# airball_display_board_v1.net
KiCad netlist of a schematic drawn in EAGLE
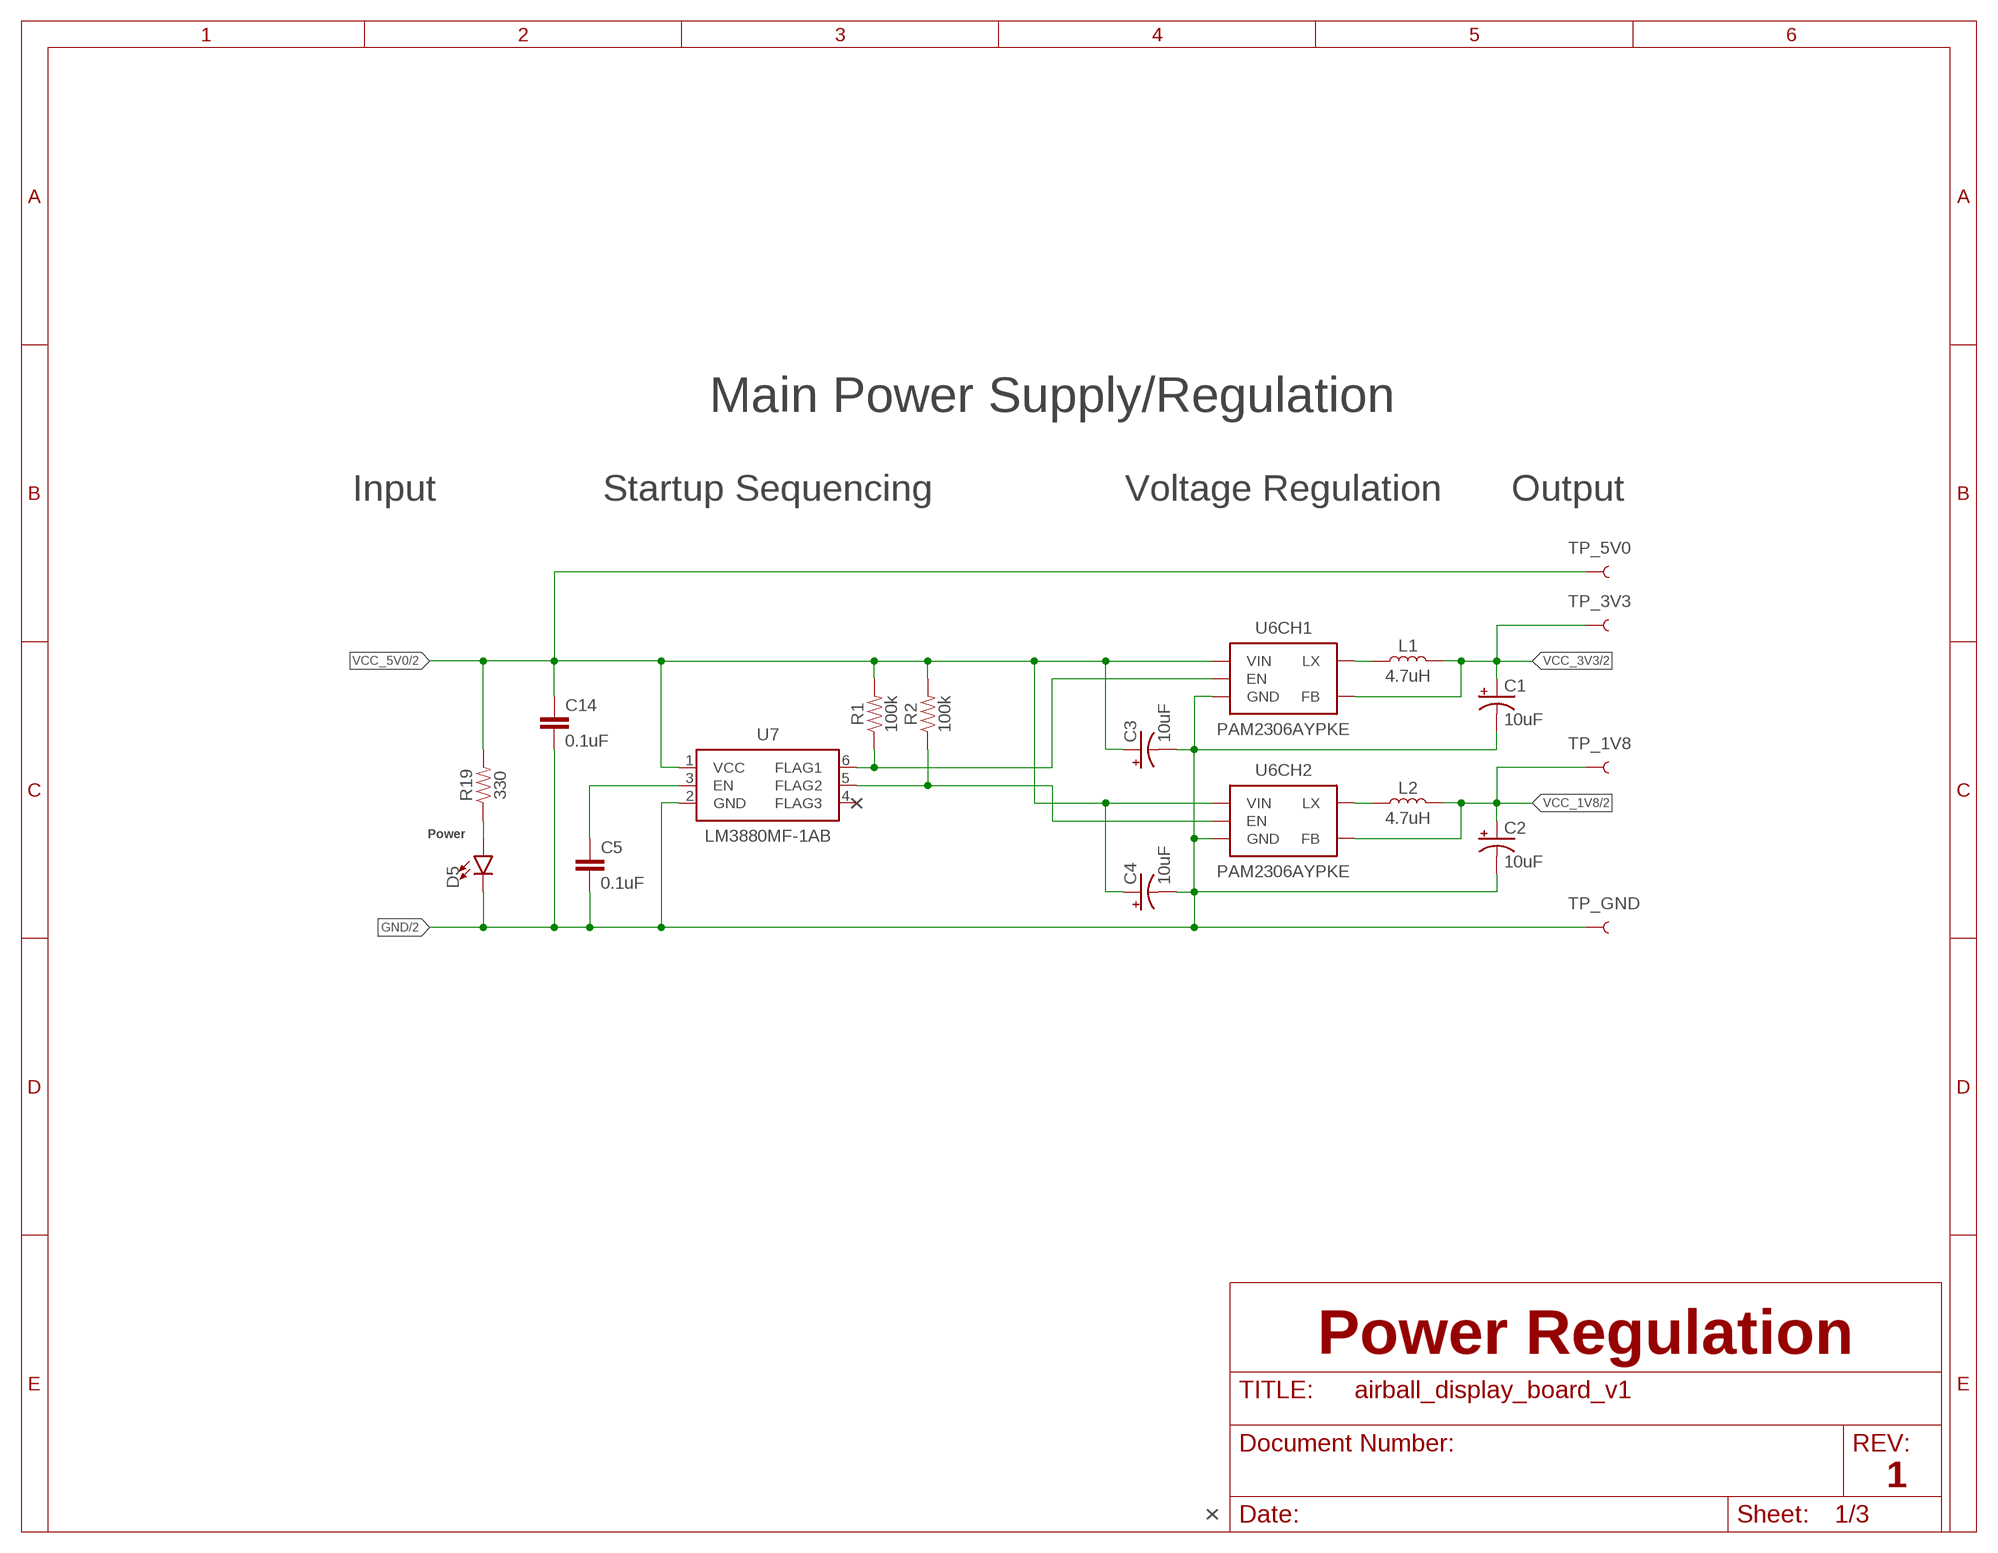
[diagram p0: schematic, sheet 1]
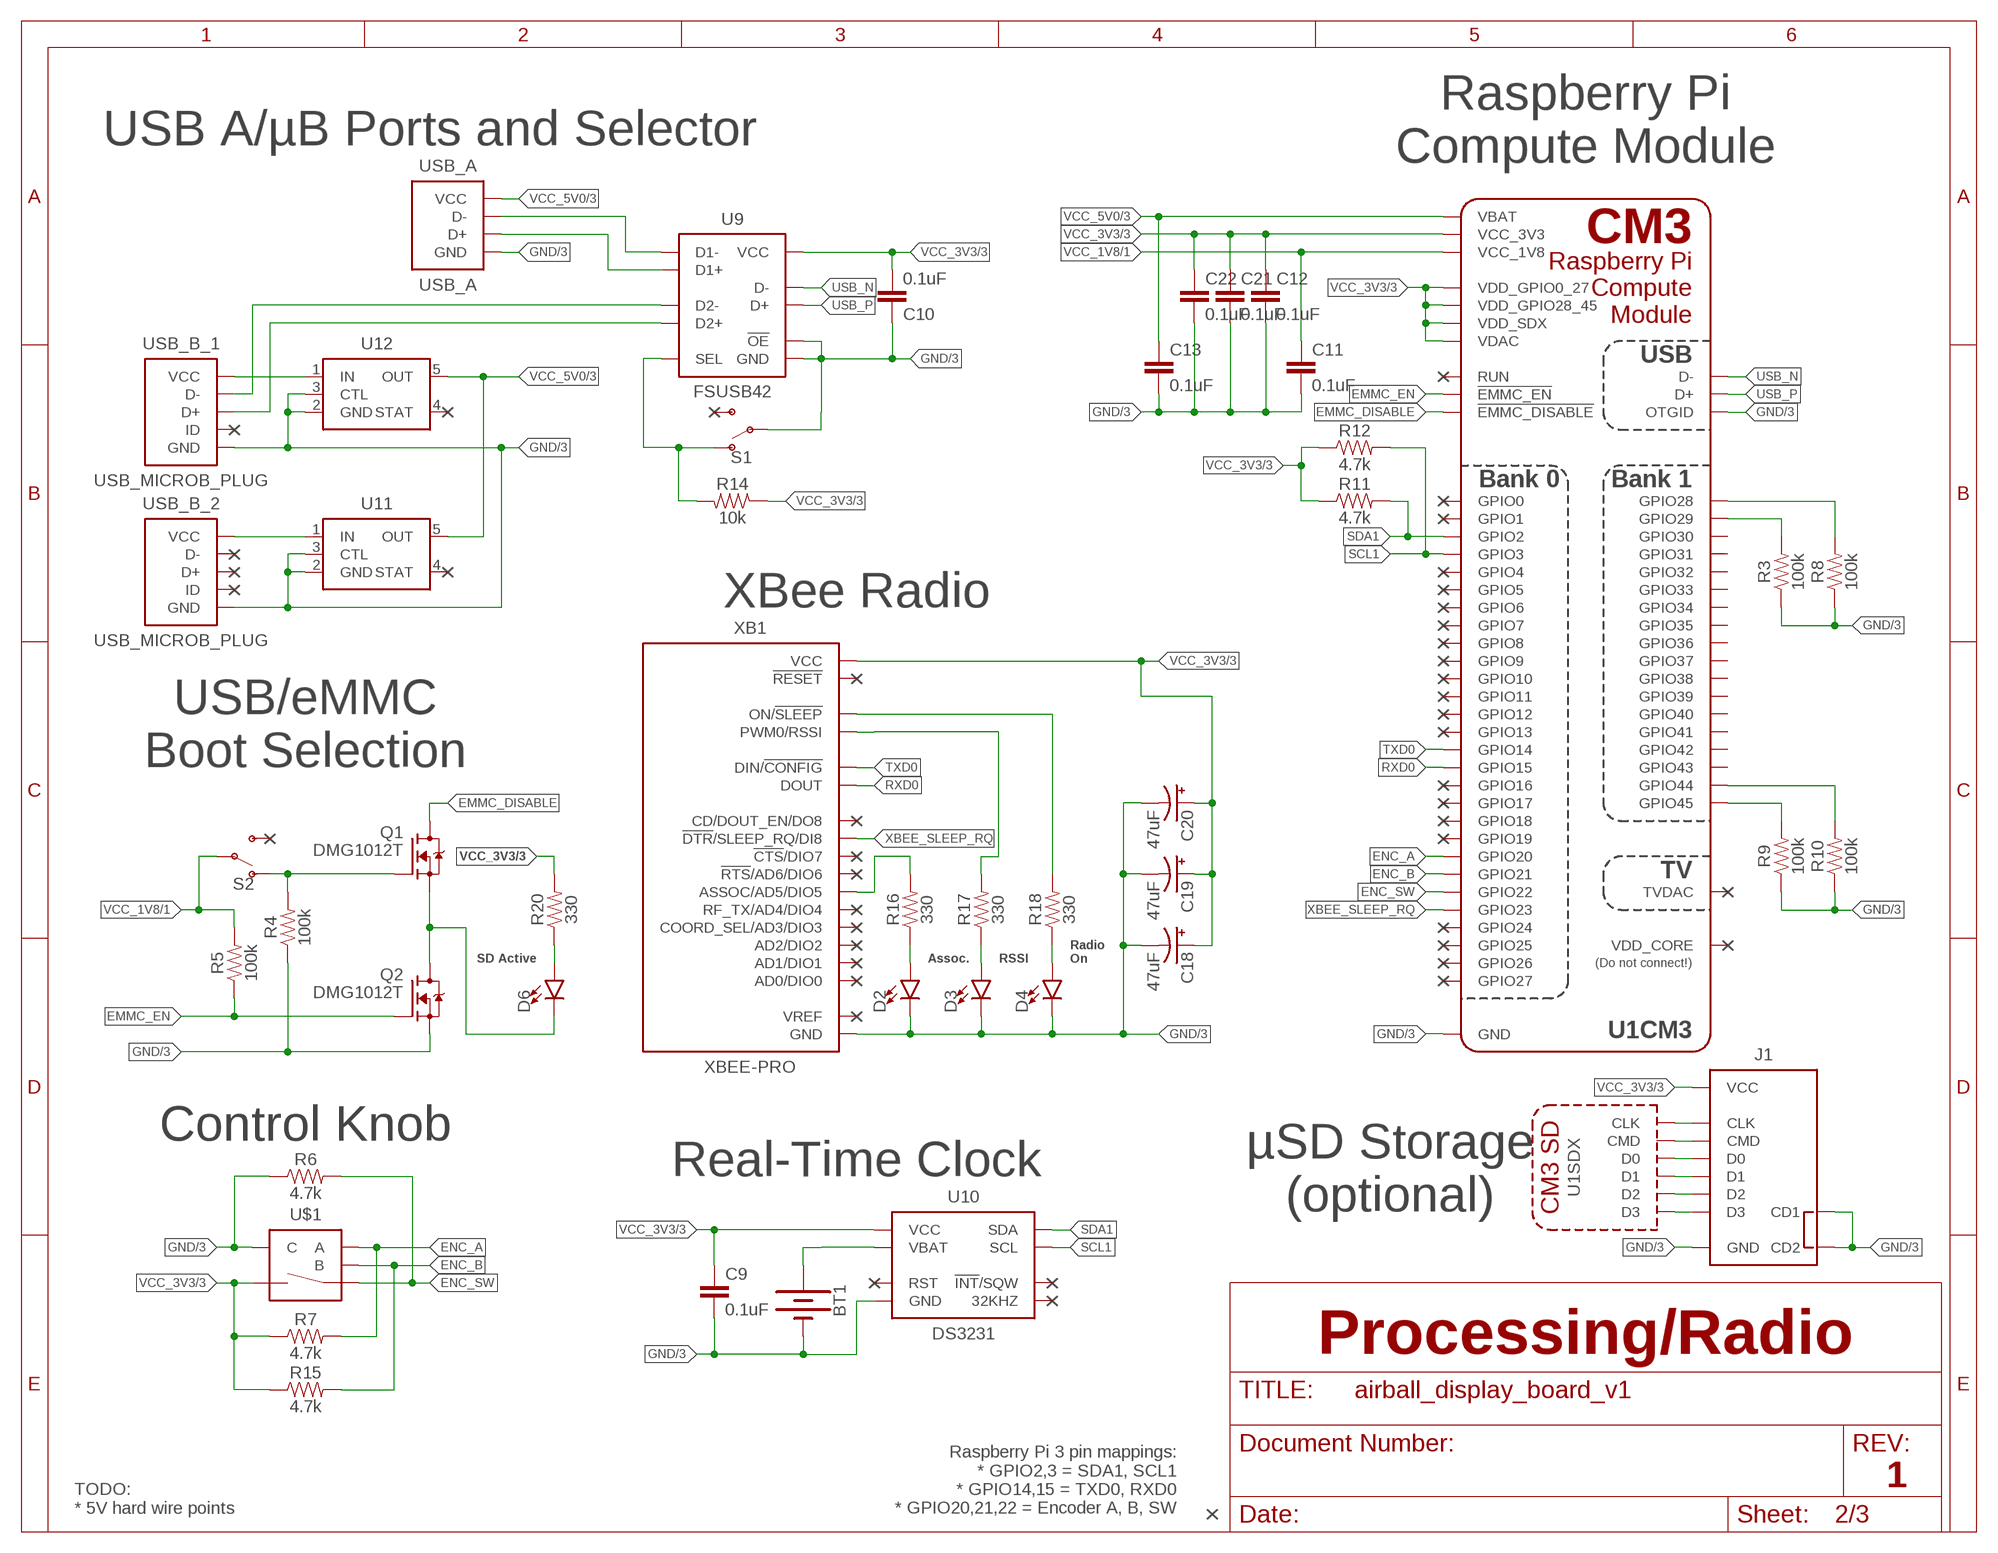
[diagram p1: schematic, sheet 2]
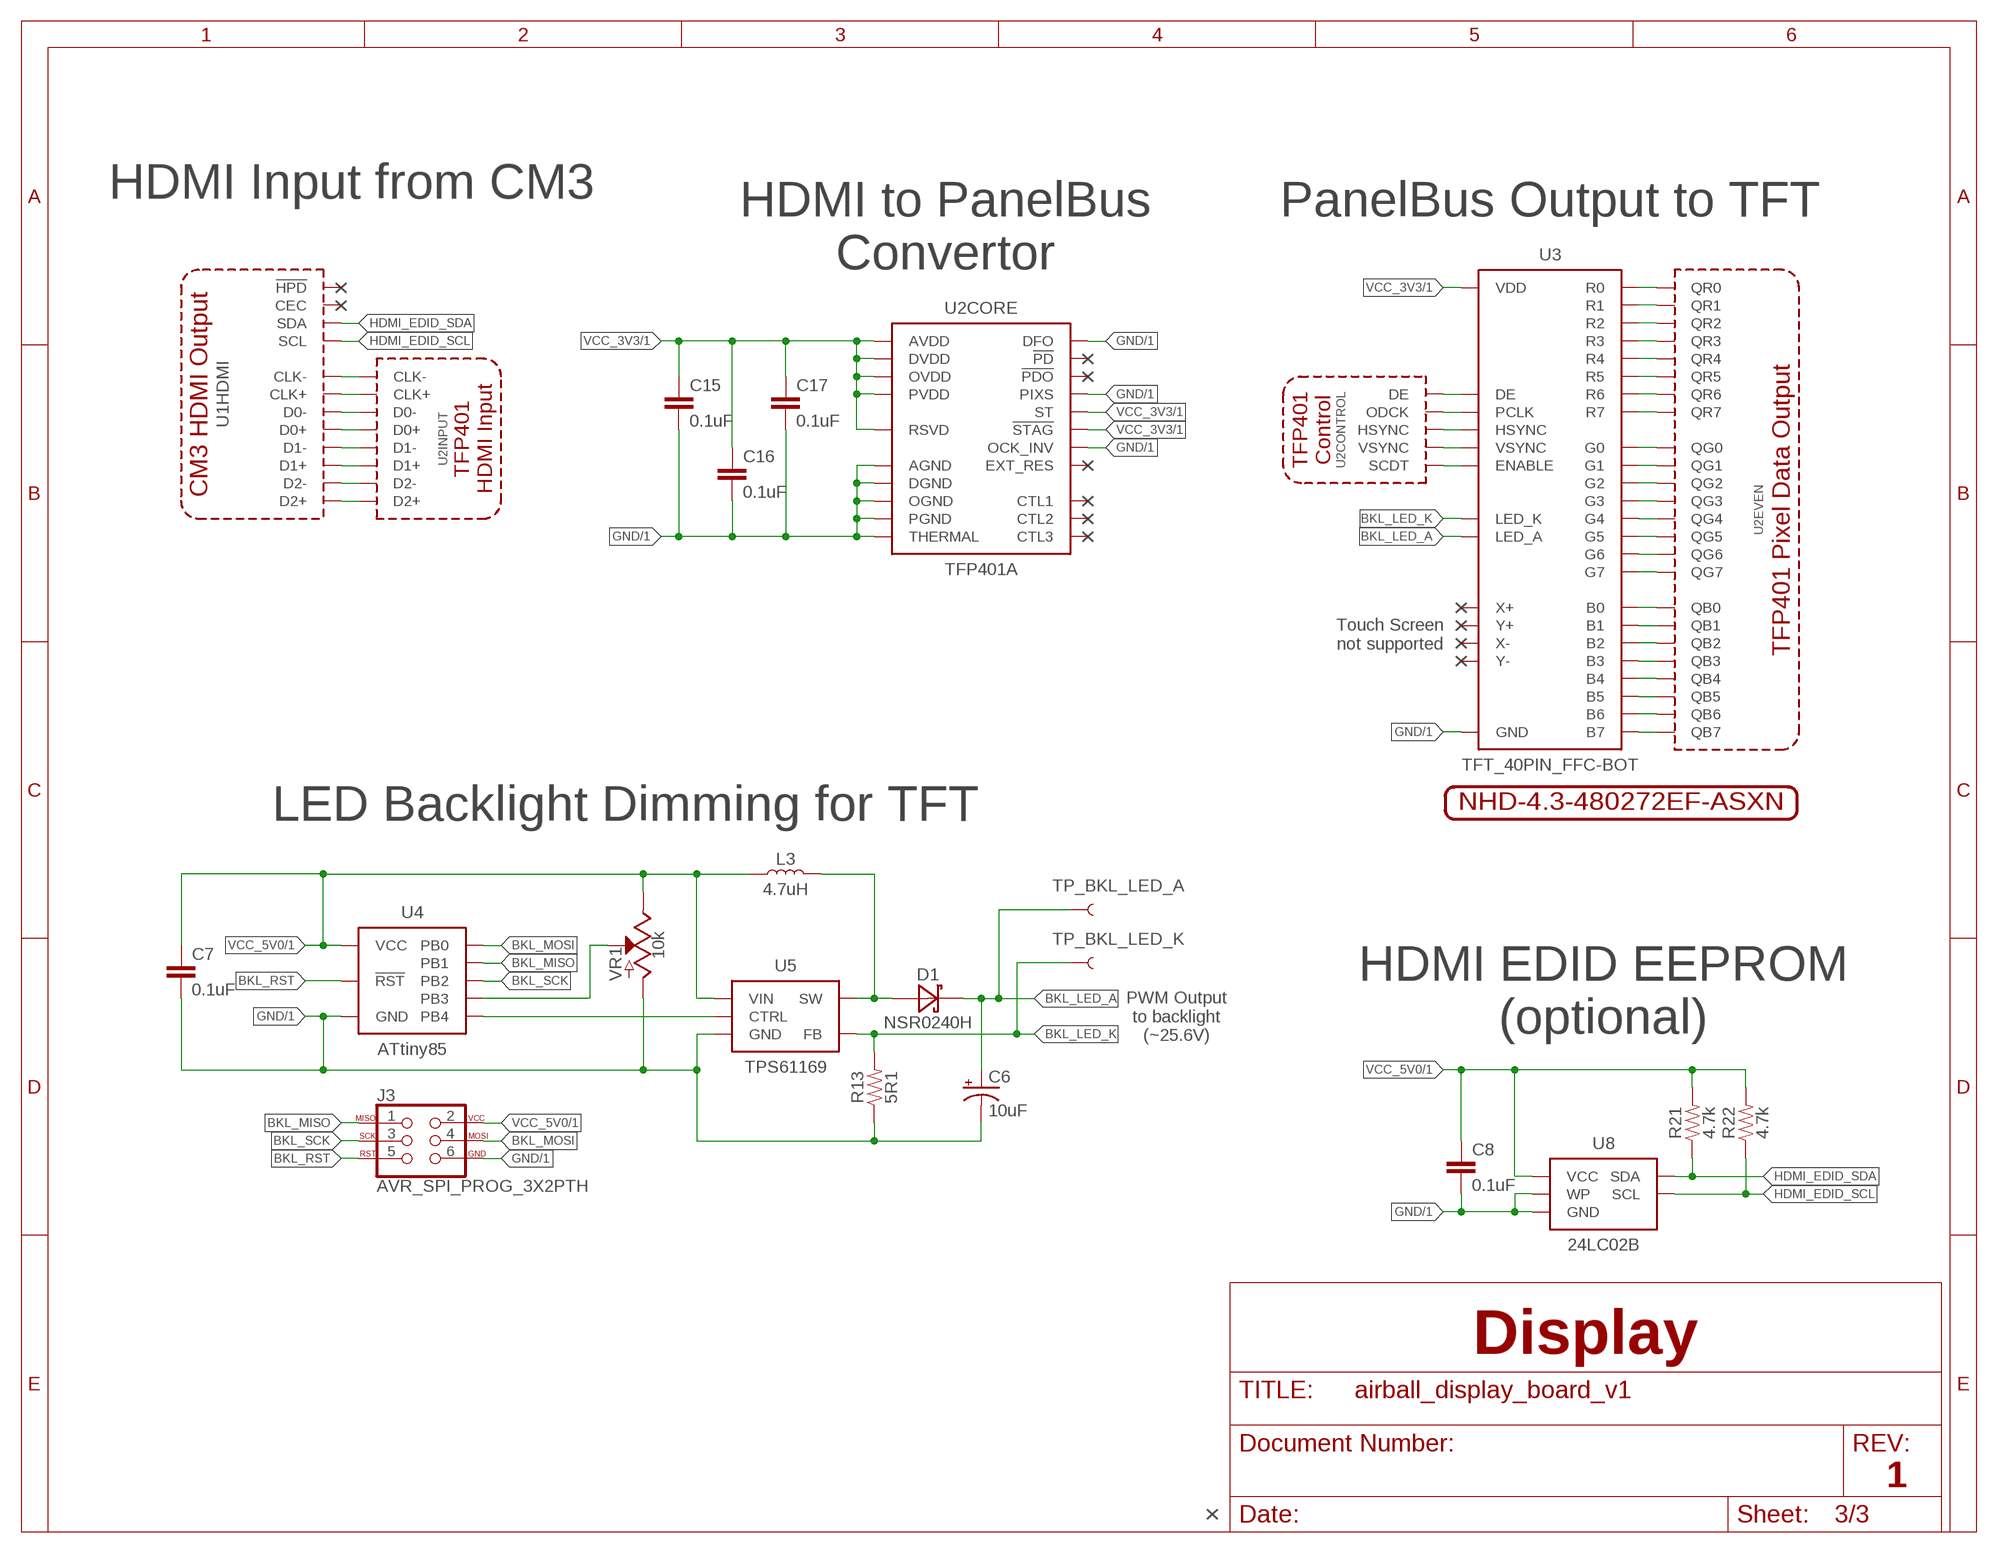
[diagram p2: schematic, sheet 3]

(export (version "E")
  (design (tool "Eeschema 10.0.6"))
  (components
    (comp (ref "BT1")
      (value "BATTERY-12MM_SMD")
      (footprint "eagle-import:BATTCON_12MM")
      (libsource (lib "eagle-import") (part "BATTERY-12MM_SMD"))
    )
    (comp (ref "C9")
      (value "0.1uF")
      (footprint "eagle-import:0603")
      (libsource (lib "eagle-import") (part "0.1UF-0603-25V-5%"))
    )
    (comp (ref "C10")
      (value "0.1uF")
      (footprint "eagle-import:0603")
      (libsource (lib "eagle-import") (part "0.1UF-0603-25V-5%"))
    )
    (comp (ref "C11")
      (value "0.1uF")
      (footprint "eagle-import:0603")
      (libsource (lib "eagle-import") (part "0.1UF-0603-25V-5%"))
    )
    (comp (ref "C12")
      (value "0.1uF")
      (footprint "eagle-import:0603")
      (libsource (lib "eagle-import") (part "0.1UF-0603-25V-5%"))
    )
    (comp (ref "C13")
      (value "0.1uF")
      (footprint "eagle-import:0603")
      (libsource (lib "eagle-import") (part "0.1UF-0603-25V-5%"))
    )
    (comp (ref "C18")
      (value "47uF")
      (footprint "eagle-import:EIA3528")
      (libsource (lib "eagle-import") (part "47UF-POLAR-EIA3528-10V-10%"))
    )
    (comp (ref "C19")
      (value "47uF")
      (footprint "eagle-import:EIA3528")
      (libsource (lib "eagle-import") (part "47UF-POLAR-EIA3528-10V-10%"))
    )
    (comp (ref "C20")
      (value "47uF")
      (footprint "eagle-import:EIA3528")
      (libsource (lib "eagle-import") (part "47UF-POLAR-EIA3528-10V-10%"))
    )
    (comp (ref "C21")
      (value "0.1uF")
      (footprint "eagle-import:0603")
      (libsource (lib "eagle-import") (part "0.1UF-0603-25V-5%"))
    )
    (comp (ref "C22")
      (value "0.1uF")
      (footprint "eagle-import:0603")
      (libsource (lib "eagle-import") (part "0.1UF-0603-25V-5%"))
    )
    (comp (ref "D2")
      (value "LED0603")
      (footprint "eagle-import:LED-0603")
      (libsource (lib "eagle-import") (part "LED0603"))
    )
    (comp (ref "D3")
      (value "LED0603")
      (footprint "eagle-import:LED-0603")
      (libsource (lib "eagle-import") (part "LED0603"))
    )
    (comp (ref "D4")
      (value "LED0603")
      (footprint "eagle-import:LED-0603")
      (libsource (lib "eagle-import") (part "LED0603"))
    )
    (comp (ref "D6")
      (value "LED0603")
      (footprint "eagle-import:LED-0603")
      (libsource (lib "eagle-import") (part "LED0603"))
    )
    (comp (ref "J1")
      (value "MICRO-SD-SD4-MOLEX_104031")
      (footprint "eagle-import:MOLEX_MICRO_SD_104031")
      (libsource (lib "eagle-import") (part "MICRO-SD-SD4-MOLEX_104031"))
    )
    (comp (ref "Q1")
      (value "DMG1012T")
      (footprint "eagle-import:SOT523-3")
      (libsource (lib "eagle-import") (part "DMG1012T"))
    )
    (comp (ref "Q2")
      (value "DMG1012T")
      (footprint "eagle-import:SOT523-3")
      (libsource (lib "eagle-import") (part "DMG1012T"))
    )
    (comp (ref "R3")
      (value "100k")
      (footprint "eagle-import:0603")
      (libsource (lib "eagle-import") (part "100KOHM-0603-1/10W-1%"))
    )
    (comp (ref "R4")
      (value "100k")
      (footprint "eagle-import:0603")
      (libsource (lib "eagle-import") (part "100KOHM-0603-1/10W-1%"))
    )
    (comp (ref "R5")
      (value "100k")
      (footprint "eagle-import:0603")
      (libsource (lib "eagle-import") (part "100KOHM-0603-1/10W-1%"))
    )
    (comp (ref "R6")
      (value "4.7k")
      (footprint "eagle-import:0603")
      (libsource (lib "eagle-import") (part "4.7KOHM-0603-1/10W-1%"))
    )
    (comp (ref "R7")
      (value "4.7k")
      (footprint "eagle-import:0603")
      (libsource (lib "eagle-import") (part "4.7KOHM-0603-1/10W-1%"))
    )
    (comp (ref "R8")
      (value "100k")
      (footprint "eagle-import:0603")
      (libsource (lib "eagle-import") (part "100KOHM-0603-1/10W-1%"))
    )
    (comp (ref "R9")
      (value "100k")
      (footprint "eagle-import:0603")
      (libsource (lib "eagle-import") (part "100KOHM-0603-1/10W-1%"))
    )
    (comp (ref "R10")
      (value "100k")
      (footprint "eagle-import:0603")
      (libsource (lib "eagle-import") (part "100KOHM-0603-1/10W-1%"))
    )
    (comp (ref "R11")
      (value "4.7k")
      (footprint "eagle-import:0603")
      (libsource (lib "eagle-import") (part "4.7KOHM-0603-1/10W-1%"))
    )
    (comp (ref "R12")
      (value "4.7k")
      (footprint "eagle-import:0603")
      (libsource (lib "eagle-import") (part "4.7KOHM-0603-1/10W-1%"))
    )
    (comp (ref "R14")
      (value "10k")
      (footprint "eagle-import:0603")
      (libsource (lib "eagle-import") (part "10KOHM-0603-1/10W-1%"))
    )
    (comp (ref "R15")
      (value "4.7k")
      (footprint "eagle-import:0603")
      (libsource (lib "eagle-import") (part "4.7KOHM-0603-1/10W-1%"))
    )
    (comp (ref "R16")
      (value "330")
      (footprint "eagle-import:0603")
      (libsource (lib "eagle-import") (part "330OHM-0603-1/10W-1%"))
    )
    (comp (ref "R17")
      (value "330")
      (footprint "eagle-import:0603")
      (libsource (lib "eagle-import") (part "330OHM-0603-1/10W-1%"))
    )
    (comp (ref "R18")
      (value "330")
      (footprint "eagle-import:0603")
      (libsource (lib "eagle-import") (part "330OHM-0603-1/10W-1%"))
    )
    (comp (ref "R20")
      (value "330")
      (footprint "eagle-import:0603")
      (libsource (lib "eagle-import") (part "330OHM-0603-1/10W-1%"))
    )
    (comp (ref "S1")
      (value "SWITCH-SPDT-SMD-RIGHT-ANGLE")
      (footprint "eagle-import:SWITCH_SPST_SMD_A")
      (libsource (lib "eagle-import") (part "SWITCH-SPDT-SMD-RIGHT-ANGLE"))
    )
    (comp (ref "S2")
      (value "SWITCH-SPDT-SMD-RIGHT-ANGLE")
      (footprint "eagle-import:SWITCH_SPST_SMD_A")
      (libsource (lib "eagle-import") (part "SWITCH-SPDT-SMD-RIGHT-ANGLE"))
    )
    (comp (ref "U$1")
      (value "ENCODER_WITH_SWITCH")
      (footprint "eagle-import:BOURNS_PEC11L")
      (libsource (lib "eagle-import") (part "ENCODER_WITH_SWITCH"))
    )
    (comp (ref "U1")
      (value "RPI_CM3-AMP_1473149")
      (footprint "eagle-import:AMP_1473149")
      (libsource (lib "eagle-import") (part "RPI_CM3-AMP_1473149"))
    )
    (comp (ref "U9")
      (value "FSUSB42")
      (footprint "eagle-import:MSOP10")
      (libsource (lib "eagle-import") (part "FSUSB42"))
    )
    (comp (ref "U10")
      (value "DS3231")
      (footprint "eagle-import:SOIC16W")
      (libsource (lib "eagle-import") (part "DS3231"))
    )
    (comp (ref "U11")
      (value "LTC4411")
      (footprint "eagle-import:SOT23-5")
      (libsource (lib "eagle-import") (part "LTC4411"))
    )
    (comp (ref "U12")
      (value "LTC4411")
      (footprint "eagle-import:SOT23-5")
      (libsource (lib "eagle-import") (part "LTC4411"))
    )
    (comp (ref "USB_A")
      (value "USB_A")
      (footprint "eagle-import:FCI_USB_A_87583")
      (libsource (lib "eagle-import") (part "USB_A"))
    )
    (comp (ref "USB_B_1")
      (value "USB_MICROB_PLUG")
      (footprint "eagle-import:USB_MICRO_B_TYCO")
      (libsource (lib "eagle-import") (part "USB_MICROB_PLUG"))
    )
    (comp (ref "USB_B_2")
      (value "USB_MICROB_PLUG")
      (footprint "eagle-import:USB_MICRO_B_TYCO")
      (libsource (lib "eagle-import") (part "USB_MICROB_PLUG"))
    )
    (comp (ref "XB1")
      (value "XBEE-PRO")
      (footprint "eagle-import:XBEE-PRO")
      (fields (field (name "MPN") "XBP24-AWI-001"))
      (libsource (lib "eagle-import") (part "XBEE-PRO"))
    )
    (comp (ref "C1")
      (value "10uF")
      (footprint "eagle-import:EIA3216")
      (libsource (lib "eagle-import") (part "10UF-POLAR-EIA3216-16V-10%(TANT)"))
    )
    (comp (ref "C2")
      (value "10uF")
      (footprint "eagle-import:EIA3216")
      (libsource (lib "eagle-import") (part "10UF-POLAR-EIA3216-16V-10%(TANT)"))
    )
    (comp (ref "C3")
      (value "10uF")
      (footprint "eagle-import:EIA3216")
      (libsource (lib "eagle-import") (part "10UF-POLAR-EIA3216-16V-10%(TANT)"))
    )
    (comp (ref "C4")
      (value "10uF")
      (footprint "eagle-import:EIA3216")
      (libsource (lib "eagle-import") (part "10UF-POLAR-EIA3216-16V-10%(TANT)"))
    )
    (comp (ref "C5")
      (value "0.1uF")
      (footprint "eagle-import:0603")
      (libsource (lib "eagle-import") (part "0.1UF-0603-25V-5%"))
    )
    (comp (ref "C14")
      (value "0.1uF")
      (footprint "eagle-import:0603")
      (libsource (lib "eagle-import") (part "0.1UF-0603-25V-5%"))
    )
    (comp (ref "D5")
      (value "LED0603")
      (footprint "eagle-import:LED-0603")
      (libsource (lib "eagle-import") (part "LED0603"))
    )
    (comp (ref "L1")
      (value "4.7uH")
      (footprint "eagle-import:INDUCTOR_SMD_4X4MM")
      (libsource (lib "eagle-import") (part "INDUCTOR-SMD_4X4"))
    )
    (comp (ref "L2")
      (value "4.7uH")
      (footprint "eagle-import:INDUCTOR_SMD_4X4MM")
      (libsource (lib "eagle-import") (part "INDUCTOR-SMD_4X4"))
    )
    (comp (ref "R1")
      (value "100k")
      (footprint "eagle-import:0603")
      (libsource (lib "eagle-import") (part "100KOHM-0603-1/10W-1%"))
    )
    (comp (ref "R2")
      (value "100k")
      (footprint "eagle-import:0603")
      (libsource (lib "eagle-import") (part "100KOHM-0603-1/10W-1%"))
    )
    (comp (ref "R19")
      (value "330")
      (footprint "eagle-import:0603")
      (libsource (lib "eagle-import") (part "330OHM-0603-1/10W-1%"))
    )
    (comp (ref "TP_1V8")
      (value "TEST-POINT3X5")
      (footprint "eagle-import:PAD.03X.05")
      (libsource (lib "eagle-import") (part "TEST-POINT3X5"))
    )
    (comp (ref "TP_3V3")
      (value "TEST-POINT3X5")
      (footprint "eagle-import:PAD.03X.05")
      (libsource (lib "eagle-import") (part "TEST-POINT3X5"))
    )
    (comp (ref "TP_5V0")
      (value "TEST-POINT3X5")
      (footprint "eagle-import:PAD.03X.05")
      (libsource (lib "eagle-import") (part "TEST-POINT3X5"))
    )
    (comp (ref "TP_GND")
      (value "TEST-POINT3X5")
      (footprint "eagle-import:PAD.03X.05")
      (libsource (lib "eagle-import") (part "TEST-POINT3X5"))
    )
    (comp (ref "U6")
      (value "PAM2306AYPKE")
      (footprint "eagle-import:WDFN12")
      (libsource (lib "eagle-import") (part "PAM2306"))
    )
    (comp (ref "U7")
      (value "LM3880MF-1AB")
      (footprint "eagle-import:SOT23-6")
      (libsource (lib "eagle-import") (part "LM3880"))
    )
    (comp (ref "C6")
      (value "10uF")
      (footprint "eagle-import:EIA3216")
      (libsource (lib "eagle-import") (part "10UF-POLAR-EIA3216-16V-10%(TANT)"))
    )
    (comp (ref "C7")
      (value "0.1uF")
      (footprint "eagle-import:0603")
      (libsource (lib "eagle-import") (part "0.1UF-0603-25V-5%"))
    )
    (comp (ref "C8")
      (value "0.1uF")
      (footprint "eagle-import:0603")
      (libsource (lib "eagle-import") (part "0.1UF-0603-25V-5%"))
    )
    (comp (ref "C15")
      (value "0.1uF")
      (footprint "eagle-import:0603")
      (libsource (lib "eagle-import") (part "0.1UF-0603-25V-5%"))
    )
    (comp (ref "C16")
      (value "0.1uF")
      (footprint "eagle-import:0603")
      (libsource (lib "eagle-import") (part "0.1UF-0603-25V-5%"))
    )
    (comp (ref "C17")
      (value "0.1uF")
      (footprint "eagle-import:0603")
      (libsource (lib "eagle-import") (part "0.1UF-0603-25V-5%"))
    )
    (comp (ref "D1")
      (value "NSR0240H")
      (footprint "eagle-import:SOD323")
      (libsource (lib "eagle-import") (part "DIODE-SCHOTTKY-SOD323"))
    )
    (comp (ref "J3")
      (value "AVR_SPI_PROG_3X2PTH")
      (footprint "eagle-import:2X3")
      (libsource (lib "eagle-import") (part "AVR_SPI_PROG_3X2PTH"))
    )
    (comp (ref "L3")
      (value "4.7uH")
      (footprint "eagle-import:INDUCTOR_SMD_4X4MM")
      (libsource (lib "eagle-import") (part "INDUCTOR-SMD_4X4"))
    )
    (comp (ref "R13")
      (value "5R1")
      (footprint "eagle-import:0603")
      (libsource (lib "eagle-import") (part "RESISTOR0603"))
    )
    (comp (ref "R21")
      (value "4.7k")
      (footprint "eagle-import:0603")
      (libsource (lib "eagle-import") (part "4.7KOHM-0603-1/10W-1%"))
    )
    (comp (ref "R22")
      (value "4.7k")
      (footprint "eagle-import:0603")
      (libsource (lib "eagle-import") (part "4.7KOHM-0603-1/10W-1%"))
    )
    (comp (ref "TP_BKL_LED_A")
      (value "TEST-POINT3X5")
      (footprint "eagle-import:PAD.03X.05")
      (libsource (lib "eagle-import") (part "TEST-POINT3X5"))
    )
    (comp (ref "TP_BKL_LED_K")
      (value "TEST-POINT3X5")
      (footprint "eagle-import:PAD.03X.05")
      (libsource (lib "eagle-import") (part "TEST-POINT3X5"))
    )
    (comp (ref "U$4")
      (value "NHD-4.3-480272EF-ASXN")
      (footprint "eagle-import:NHD-4.3-480272EF-ASXN")
      (libsource (lib "eagle-import") (part "NHD-4.3-480272EF-ASXN"))
    )
    (comp (ref "U2")
      (value "TFP401A")
      (footprint "eagle-import:TQFP100_POWER_LITE")
      (libsource (lib "eagle-import") (part "TFP401-POWER_LITE"))
    )
    (comp (ref "U3")
      (value "TFT_40PIN_FFC-BOT")
      (footprint "eagle-import:HIROSE_FFC40_FH12-40S-0.5SH")
      (libsource (lib "eagle-import") (part "TFT_40PIN_FFC-BOT"))
    )
    (comp (ref "U4")
      (value "ATtiny85")
      (footprint "eagle-import:SOIC8-5.4")
      (libsource (lib "eagle-import") (part "ATTINY25/45/85"))
    )
    (comp (ref "U5")
      (value "TPS61169")
      (footprint "eagle-import:SOT353-5")
      (libsource (lib "eagle-import") (part "TPS61169"))
    )
    (comp (ref "U8")
      (value "24LC02B")
      (footprint "eagle-import:SOT23-5")
      (libsource (lib "eagle-import") (part "24LC02B"))
    )
    (comp (ref "VR1")
      (value "10k")
      (footprint "eagle-import:BOURNS_PTV09A")
      (libsource (lib "eagle-import") (part "POTENTIOMETERPTV09A"))
    )
  )
  (nets
    (net (code "1") (name "BKL_LED_A") (class "Default")
      (node (ref "C6") (pin "+") (pinfunction "+_+") (pintype "passive"))
      (node (ref "D1") (pin "K") (pinfunction "C_K") (pintype "passive"))
      (node (ref "TP_BKL_LED_A") (pin "P$1") (pinfunction "1_P$1") (pintype "bidirectional"))
      (node (ref "U3") (pin "2") (pinfunction "LED_A_2") (pintype "power_in"))
    )
    (net (code "2") (name "BKL_LED_K") (class "Default")
      (node (ref "R13") (pin "2") (pinfunction "2_2") (pintype "passive"))
      (node (ref "TP_BKL_LED_K") (pin "P$1") (pinfunction "1_P$1") (pintype "bidirectional"))
      (node (ref "U3") (pin "1") (pinfunction "LED_K_1") (pintype "power_in"))
      (node (ref "U5") (pin "3") (pinfunction "FB_3") (pintype "input"))
    )
    (net (code "3") (name "BKL_MISO") (class "Default")
      (node (ref "J3") (pin "1") (pinfunction "1_1") (pintype "passive"))
      (node (ref "U4") (pin "6") (pinfunction "PB1_6") (pintype "bidirectional"))
    )
    (net (code "4") (name "BKL_MOSI") (class "Default")
      (node (ref "J3") (pin "4") (pinfunction "4_4") (pintype "passive"))
      (node (ref "U4") (pin "5") (pinfunction "PB0_5") (pintype "bidirectional"))
    )
    (net (code "5") (name "BKL_RST") (class "Default")
      (node (ref "J3") (pin "5") (pinfunction "5_5") (pintype "passive"))
      (node (ref "U4") (pin "1") (pinfunction "~{RST}_1") (pintype "input"))
    )
    (net (code "6") (name "BKL_SCK") (class "Default")
      (node (ref "J3") (pin "3") (pinfunction "3_3") (pintype "passive"))
      (node (ref "U4") (pin "7") (pinfunction "PB2_7") (pintype "bidirectional"))
    )
    (net (code "7") (name "EMMC_DISABLE") (class "Default")
      (node (ref "Q1") (pin "2") (pinfunction "D_2") (pintype "passive"))
      (node (ref "U1") (pin "2") (pinfunction "~{EMMC_DISABLE}_2") (pintype "input"))
    )
    (net (code "8") (name "EMMC_EN") (class "Default")
      (node (ref "Q2") (pin "1") (pinfunction "G_1") (pintype "passive"))
      (node (ref "R5") (pin "1") (pinfunction "1_1") (pintype "passive"))
      (node (ref "U1") (pin "90") (pinfunction "~{EMMC_EN}_90") (pintype "output"))
    )
    (net (code "9") (name "ENC_A") (class "Default")
      (node (ref "R7") (pin "2") (pinfunction "2_2") (pintype "passive"))
      (node (ref "U$1") (pin "A") (pinfunction "A_A") (pintype "output"))
      (node (ref "U1") (pin "69") (pinfunction "GPIO20_69") (pintype "bidirectional"))
    )
    (net (code "10") (name "ENC_B") (class "Default")
      (node (ref "R15") (pin "2") (pinfunction "2_2") (pintype "passive"))
      (node (ref "U$1") (pin "B") (pinfunction "B_B") (pintype "output"))
      (node (ref "U1") (pin "71") (pinfunction "GPIO21_71") (pintype "bidirectional"))
    )
    (net (code "11") (name "ENC_SW") (class "Default")
      (node (ref "R6") (pin "2") (pinfunction "2_2") (pintype "passive"))
      (node (ref "U$1") (pin "1") (pinfunction "SW+_1") (pintype "bidirectional"))
      (node (ref "U1") (pin "75") (pinfunction "GPIO22_75") (pintype "bidirectional"))
    )
    (net (code "12") (name "GND") (class "Default")
      (node (ref "BT1") (pin "GND") (pinfunction "-_GND") (pintype "power_in"))
      (node (ref "C1") (pin "-") (pinfunction "-_-") (pintype "passive"))
      (node (ref "C10") (pin "1") (pinfunction "1_1") (pintype "passive"))
      (node (ref "C11") (pin "2") (pinfunction "2_2") (pintype "passive"))
      (node (ref "C12") (pin "2") (pinfunction "2_2") (pintype "passive"))
      (node (ref "C13") (pin "2") (pinfunction "2_2") (pintype "passive"))
      (node (ref "C14") (pin "2") (pinfunction "2_2") (pintype "passive"))
      (node (ref "C15") (pin "2") (pinfunction "2_2") (pintype "passive"))
      (node (ref "C16") (pin "2") (pinfunction "2_2") (pintype "passive"))
      (node (ref "C17") (pin "2") (pinfunction "2_2") (pintype "passive"))
      (node (ref "C18") (pin "C") (pinfunction "-_C") (pintype "passive"))
      (node (ref "C19") (pin "C") (pinfunction "-_C") (pintype "passive"))
      (node (ref "C2") (pin "-") (pinfunction "-_-") (pintype "passive"))
      (node (ref "C20") (pin "C") (pinfunction "-_C") (pintype "passive"))
      (node (ref "C21") (pin "2") (pinfunction "2_2") (pintype "passive"))
      (node (ref "C22") (pin "2") (pinfunction "2_2") (pintype "passive"))
      (node (ref "C3") (pin "-") (pinfunction "-_-") (pintype "passive"))
      (node (ref "C4") (pin "-") (pinfunction "-_-") (pintype "passive"))
      (node (ref "C5") (pin "2") (pinfunction "2_2") (pintype "passive"))
      (node (ref "C6") (pin "-") (pinfunction "-_-") (pintype "passive"))
      (node (ref "C7") (pin "2") (pinfunction "2_2") (pintype "passive"))
      (node (ref "C8") (pin "2") (pinfunction "2_2") (pintype "passive"))
      (node (ref "C9") (pin "2") (pinfunction "2_2") (pintype "passive"))
      (node (ref "D2") (pin "C") (pinfunction "C_C") (pintype "passive"))
      (node (ref "D3") (pin "C") (pinfunction "C_C") (pintype "passive"))
      (node (ref "D4") (pin "C") (pinfunction "C_C") (pintype "passive"))
      (node (ref "D5") (pin "C") (pinfunction "C_C") (pintype "passive"))
      (node (ref "J1") (pin "6") (pinfunction "GND_6") (pintype "power_in"))
      (node (ref "J1") (pin "CD1") (pinfunction "CD1_CD1") (pintype "bidirectional"))
      (node (ref "J1") (pin "CD2") (pinfunction "CD2_CD2") (pintype "bidirectional"))
      (node (ref "J1") (pin "SH@1") (pinfunction "GND_SH@1") (pintype "power_in"))
      (node (ref "J1") (pin "SH@2") (pinfunction "GND_SH@2") (pintype "power_in"))
      (node (ref "J1") (pin "SH@3") (pinfunction "GND_SH@3") (pintype "power_in"))
      (node (ref "J1") (pin "SH@4") (pinfunction "GND_SH@4") (pintype "power_in"))
      (node (ref "J3") (pin "6") (pinfunction "6_6") (pintype "passive"))
      (node (ref "Q2") (pin "3") (pinfunction "S_3") (pintype "passive"))
      (node (ref "R10") (pin "1") (pinfunction "1_1") (pintype "passive"))
      (node (ref "R13") (pin "1") (pinfunction "1_1") (pintype "passive"))
      (node (ref "R3") (pin "1") (pinfunction "1_1") (pintype "passive"))
      (node (ref "R4") (pin "1") (pinfunction "1_1") (pintype "passive"))
      (node (ref "R6") (pin "1") (pinfunction "1_1") (pintype "passive"))
      (node (ref "R8") (pin "1") (pinfunction "1_1") (pintype "passive"))
      (node (ref "R9") (pin "1") (pinfunction "1_1") (pintype "passive"))
      (node (ref "S1") (pin "2") (pinfunction "P_2") (pintype "passive"))
      (node (ref "TP_GND") (pin "P$1") (pinfunction "1_P$1") (pintype "bidirectional"))
      (node (ref "U$1") (pin "C") (pinfunction "C_C") (pintype "input"))
      (node (ref "U1") (pin "1") (pinfunction "GND_1") (pintype "power_in"))
      (node (ref "U1") (pin "103") (pinfunction "GND_103") (pintype "power_in"))
      (node (ref "U1") (pin "104") (pinfunction "GND_104") (pintype "power_in"))
      (node (ref "U1") (pin "109") (pinfunction "GND_109") (pintype "power_in"))
      (node (ref "U1") (pin "110") (pinfunction "GND_110") (pintype "power_in"))
      (node (ref "U1") (pin "115") (pinfunction "GND_115") (pintype "power_in"))
      (node (ref "U1") (pin "116") (pinfunction "GND_116") (pintype "power_in"))
      (node (ref "U1") (pin "121") (pinfunction "GND_121") (pintype "power_in"))
      (node (ref "U1") (pin "122") (pinfunction "GND_122") (pintype "power_in"))
      (node (ref "U1") (pin "127") (pinfunction "GND_127") (pintype "power_in"))
      (node (ref "U1") (pin "13") (pinfunction "GND_13") (pintype "power_in"))
      (node (ref "U1") (pin "133") (pinfunction "GND_133") (pintype "power_in"))
      (node (ref "U1") (pin "134") (pinfunction "GND_134") (pintype "power_in"))
      (node (ref "U1") (pin "139") (pinfunction "GND_139") (pintype "power_in"))
      (node (ref "U1") (pin "14") (pinfunction "GND_14") (pintype "power_in"))
      (node (ref "U1") (pin "140") (pinfunction "GND_140") (pintype "power_in"))
      (node (ref "U1") (pin "145") (pinfunction "GND_145") (pintype "power_in"))
      (node (ref "U1") (pin "146") (pinfunction "GND_146") (pintype "power_in"))
      (node (ref "U1") (pin "151") (pinfunction "GND_151") (pintype "power_in"))
      (node (ref "U1") (pin "152") (pinfunction "GND_152") (pintype "power_in"))
      (node (ref "U1") (pin "157") (pinfunction "GND_157") (pintype "power_in"))
      (node (ref "U1") (pin "163") (pinfunction "GND_163") (pintype "power_in"))
      (node (ref "U1") (pin "164") (pinfunction "GND_164") (pintype "power_in"))
      (node (ref "U1") (pin "168") (pinfunction "OTGID_168") (pintype "input"))
      (node (ref "U1") (pin "169") (pinfunction "GND_169") (pintype "power_in"))
      (node (ref "U1") (pin "170") (pinfunction "GND_170") (pintype "power_in"))
      (node (ref "U1") (pin "181") (pinfunction "GND_181") (pintype "power_in"))
      (node (ref "U1") (pin "182") (pinfunction "GND_182") (pintype "power_in"))
      (node (ref "U1") (pin "187") (pinfunction "GND_187") (pintype "power_in"))
      (node (ref "U1") (pin "188") (pinfunction "GND_188") (pintype "power_in"))
      (node (ref "U1") (pin "19") (pinfunction "GND_19") (pintype "power_in"))
      (node (ref "U1") (pin "195") (pinfunction "GND_195") (pintype "power_in"))
      (node (ref "U1") (pin "196") (pinfunction "GND_196") (pintype "power_in"))
      (node (ref "U1") (pin "20") (pinfunction "GND_20") (pintype "power_in"))
      (node (ref "U1") (pin "25") (pinfunction "GND_25") (pintype "power_in"))
      (node (ref "U1") (pin "26") (pinfunction "GND_26") (pintype "power_in"))
      (node (ref "U1") (pin "31") (pinfunction "GND_31") (pintype "power_in"))
      (node (ref "U1") (pin "32") (pinfunction "GND_32") (pintype "power_in"))
      (node (ref "U1") (pin "37") (pinfunction "GND_37") (pintype "power_in"))
      (node (ref "U1") (pin "38") (pinfunction "GND_38") (pintype "power_in"))
      (node (ref "U1") (pin "43") (pinfunction "GND_43") (pintype "power_in"))
      (node (ref "U1") (pin "44") (pinfunction "GND_44") (pintype "power_in"))
      (node (ref "U1") (pin "49") (pinfunction "GND_49") (pintype "power_in"))
      (node (ref "U1") (pin "50") (pinfunction "GND_50") (pintype "power_in"))
      (node (ref "U1") (pin "55") (pinfunction "GND_55") (pintype "power_in"))
      (node (ref "U1") (pin "56") (pinfunction "GND_56") (pintype "power_in"))
      (node (ref "U1") (pin "61") (pinfunction "GND_61") (pintype "power_in"))
      (node (ref "U1") (pin "62") (pinfunction "GND_62") (pintype "power_in"))
      (node (ref "U1") (pin "67") (pinfunction "GND_67") (pintype "power_in"))
      (node (ref "U1") (pin "68") (pinfunction "GND_68") (pintype "power_in"))
      (node (ref "U1") (pin "7") (pinfunction "GND_7") (pintype "power_in"))
      (node (ref "U1") (pin "73") (pinfunction "GND_73") (pintype "power_in"))
      (node (ref "U1") (pin "74") (pinfunction "GND_74") (pintype "power_in"))
      (node (ref "U1") (pin "79") (pinfunction "GND_79") (pintype "power_in"))
      (node (ref "U1") (pin "8") (pinfunction "GND_8") (pintype "power_in"))
      (node (ref "U1") (pin "80") (pinfunction "GND_80") (pintype "power_in"))
      (node (ref "U1") (pin "85") (pinfunction "GND_85") (pintype "power_in"))
      (node (ref "U1") (pin "86") (pinfunction "GND_86") (pintype "power_in"))
      (node (ref "U1") (pin "91") (pinfunction "GND_91") (pintype "power_in"))
      (node (ref "U1") (pin "92") (pinfunction "GND_92") (pintype "power_in"))
      (node (ref "U1") (pin "97") (pinfunction "GND_97") (pintype "power_in"))
      (node (ref "U1") (pin "98") (pinfunction "GND_98") (pintype "power_in"))
      (node (ref "U10") (pin "10") (pinfunction "GND_10") (pintype "power_in"))
      (node (ref "U10") (pin "11") (pinfunction "GND_11") (pintype "power_in"))
      (node (ref "U10") (pin "12") (pinfunction "GND_12") (pintype "power_in"))
      (node (ref "U10") (pin "13") (pinfunction "GND_13") (pintype "power_in"))
      (node (ref "U10") (pin "5") (pinfunction "GND_5") (pintype "power_in"))
      (node (ref "U10") (pin "6") (pinfunction "GND_6") (pintype "power_in"))
      (node (ref "U10") (pin "7") (pinfunction "GND_7") (pintype "power_in"))
      (node (ref "U10") (pin "8") (pinfunction "GND_8") (pintype "power_in"))
      (node (ref "U10") (pin "9") (pinfunction "GND_9") (pintype "power_in"))
      (node (ref "U11") (pin "2") (pinfunction "GND_2") (pintype "power_in"))
      (node (ref "U11") (pin "3") (pinfunction "CTL_3") (pintype "input"))
      (node (ref "U12") (pin "2") (pinfunction "GND_2") (pintype "power_in"))
      (node (ref "U12") (pin "3") (pinfunction "CTL_3") (pintype "input"))
      (node (ref "U2") (pin "1") (pinfunction "DFO_1") (pintype "input"))
      (node (ref "U2") (pin "100") (pinfunction "OCK_INV_100") (pintype "input"))
      (node (ref "U2") (pin "19") (pinfunction "OGND_19") (pintype "power_in"))
      (node (ref "U2") (pin "28") (pinfunction "OGND_28") (pintype "power_in"))
      (node (ref "U2") (pin "39") (pinfunction "DGND_39") (pintype "power_in"))
      (node (ref "U2") (pin "4") (pinfunction "PIXS_4") (pintype "input"))
      (node (ref "U2") (pin "45") (pinfunction "OGND_45") (pintype "power_in"))
      (node (ref "U2") (pin "5") (pinfunction "DGND_5") (pintype "power_in"))
      (node (ref "U2") (pin "58") (pinfunction "OGND_58") (pintype "power_in"))
      (node (ref "U2") (pin "68") (pinfunction "DGND_68") (pintype "power_in"))
      (node (ref "U2") (pin "76") (pinfunction "OGND_76") (pintype "power_in"))
      (node (ref "U2") (pin "79") (pinfunction "AGND_79") (pintype "power_in"))
      (node (ref "U2") (pin "83") (pinfunction "AGND_83") (pintype "power_in"))
      (node (ref "U2") (pin "87") (pinfunction "AGND_87") (pintype "power_in"))
      (node (ref "U2") (pin "89") (pinfunction "AGND_89") (pintype "power_in"))
      (node (ref "U2") (pin "92") (pinfunction "AGND_92") (pintype "power_in"))
      (node (ref "U2") (pin "98") (pinfunction "PGND_98") (pintype "power_in"))
      (node (ref "U2") (pin "TH21") (pinfunction "THERMAL_TH21") (pintype "power_in"))
      (node (ref "U2") (pin "TH22") (pinfunction "THERMAL_TH22") (pintype "power_in"))
      (node (ref "U2") (pin "TH23") (pinfunction "THERMAL_TH23") (pintype "power_in"))
      (node (ref "U2") (pin "TH24") (pinfunction "THERMAL_TH24") (pintype "power_in"))
      (node (ref "U2") (pin "TH25") (pinfunction "THERMAL_TH25") (pintype "power_in"))
      (node (ref "U2") (pin "TH30") (pinfunction "THERMAL_TH30") (pintype "power_in"))
      (node (ref "U2") (pin "TH34") (pinfunction "THERMAL_TH34") (pintype "power_in"))
      (node (ref "U2") (pin "TH39") (pinfunction "THERMAL_TH39") (pintype "power_in"))
      (node (ref "U2") (pin "TH43") (pinfunction "THERMAL_TH43") (pintype "power_in"))
      (node (ref "U2") (pin "TH48") (pinfunction "THERMAL_TH48") (pintype "power_in"))
      (node (ref "U2") (pin "TH52") (pinfunction "THERMAL_TH52") (pintype "power_in"))
      (node (ref "U2") (pin "TH57") (pinfunction "THERMAL_TH57") (pintype "power_in"))
      (node (ref "U2") (pin "TH58") (pinfunction "THERMAL_TH58") (pintype "power_in"))
      (node (ref "U2") (pin "TH59") (pinfunction "THERMAL_TH59") (pintype "power_in"))
      (node (ref "U2") (pin "TH60") (pinfunction "THERMAL_TH60") (pintype "power_in"))
      (node (ref "U2") (pin "TH61") (pinfunction "THERMAL_TH61") (pintype "power_in"))
      (node (ref "U2") (pin "THA") (pinfunction "THERMAL_THA") (pintype "power_in"))
      (node (ref "U2") (pin "THB") (pinfunction "THERMAL_THB") (pintype "power_in"))
      (node (ref "U3") (pin "29") (pinfunction "GND_29") (pintype "power_in"))
      (node (ref "U3") (pin "3") (pinfunction "GND_3") (pintype "power_in"))
      (node (ref "U3") (pin "36") (pinfunction "GND_36") (pintype "power_in"))
      (node (ref "U4") (pin "4") (pinfunction "GND_4") (pintype "power_in"))
      (node (ref "U5") (pin "2") (pinfunction "GND_2") (pintype "power_in"))
      (node (ref "U6") (pin "3") (pinfunction "GND_3") (pintype "input"))
      (node (ref "U6") (pin "9") (pinfunction "GND_9") (pintype "input"))
      (node (ref "U6") (pin "TH") (pinfunction "GND_TH") (pintype "input"))
      (node (ref "U7") (pin "2") (pinfunction "GND_2") (pintype "power_in"))
      (node (ref "U8") (pin "2") (pinfunction "GND_2") (pintype "power_in"))
      (node (ref "U8") (pin "5") (pinfunction "WP_5") (pintype "input"))
      (node (ref "U9") (pin "10") (pinfunction "~{OE}_10") (pintype "bidirectional"))
      (node (ref "U9") (pin "5") (pinfunction "GND_5") (pintype "bidirectional"))
      (node (ref "USB_A") (pin "GND") (pinfunction "GND_GND") (pintype "power_in"))
      (node (ref "USB_A") (pin "SH@1") (pinfunction "GND_SH@1") (pintype "power_in"))
      (node (ref "USB_A") (pin "SH@2") (pinfunction "GND_SH@2") (pintype "power_in"))
      (node (ref "USB_B_1") (pin "5") (pinfunction "GND_5") (pintype "power_in"))
      (node (ref "USB_B_1") (pin "SH@1") (pinfunction "GND_SH@1") (pintype "power_in"))
      (node (ref "USB_B_1") (pin "SH@2") (pinfunction "GND_SH@2") (pintype "power_in"))
      (node (ref "USB_B_1") (pin "SH@3") (pinfunction "GND_SH@3") (pintype "power_in"))
      (node (ref "USB_B_1") (pin "SH@4") (pinfunction "GND_SH@4") (pintype "power_in"))
      (node (ref "USB_B_2") (pin "5") (pinfunction "GND_5") (pintype "power_in"))
      (node (ref "USB_B_2") (pin "SH@1") (pinfunction "GND_SH@1") (pintype "power_in"))
      (node (ref "USB_B_2") (pin "SH@2") (pinfunction "GND_SH@2") (pintype "power_in"))
      (node (ref "USB_B_2") (pin "SH@3") (pinfunction "GND_SH@3") (pintype "power_in"))
      (node (ref "USB_B_2") (pin "SH@4") (pinfunction "GND_SH@4") (pintype "power_in"))
      (node (ref "VR1") (pin "1") (pinfunction "A_1") (pintype "passive"))
      (node (ref "XB1") (pin "10") (pinfunction "GND_10") (pintype "power_in"))
    )
    (net (code "13") (name "HDMI_EDID_SCL") (class "Default")
      (node (ref "R22") (pin "1") (pinfunction "1_1") (pintype "passive"))
      (node (ref "U1") (pin "175") (pinfunction "SCL_175") (pintype "output"))
      (node (ref "U8") (pin "1") (pinfunction "SCL_1") (pintype "input"))
    )
    (net (code "14") (name "HDMI_EDID_SDA") (class "Default")
      (node (ref "R21") (pin "1") (pinfunction "1_1") (pintype "passive"))
      (node (ref "U1") (pin "173") (pinfunction "SDA_173") (pintype "bidirectional"))
      (node (ref "U8") (pin "3") (pinfunction "SDA_3") (pintype "output"))
    )
    (net (code "15") (name "Net-(BT1-+)") (class "Default")
      (node (ref "BT1") (pin "PWR@1") (pinfunction "+_PWR@1") (pintype "power_in"))
      (node (ref "U10") (pin "14") (pinfunction "VBAT_14") (pintype "power_in"))
    )
    (net (code "16") (name "Net-(D2-PadA)") (class "Default")
      (node (ref "D2") (pin "A") (pinfunction "A_A") (pintype "passive"))
      (node (ref "R16") (pin "1") (pinfunction "1_1") (pintype "passive"))
    )
    (net (code "17") (name "Net-(D3-PadA)") (class "Default")
      (node (ref "D3") (pin "A") (pinfunction "A_A") (pintype "passive"))
      (node (ref "R17") (pin "1") (pinfunction "1_1") (pintype "passive"))
    )
    (net (code "18") (name "Net-(D4-PadA)") (class "Default")
      (node (ref "D4") (pin "A") (pinfunction "A_A") (pintype "passive"))
      (node (ref "R18") (pin "1") (pinfunction "1_1") (pintype "passive"))
    )
    (net (code "19") (name "Net-(D5-PadA)") (class "Default")
      (node (ref "D5") (pin "A") (pinfunction "A_A") (pintype "passive"))
      (node (ref "R19") (pin "1") (pinfunction "1_1") (pintype "passive"))
    )
    (net (code "20") (name "Net-(D6-PadA)") (class "Default")
      (node (ref "D6") (pin "A") (pinfunction "A_A") (pintype "passive"))
      (node (ref "R20") (pin "1") (pinfunction "1_1") (pintype "passive"))
    )
    (net (code "21") (name "Net-(J1-CLK)") (class "Default")
      (node (ref "J1") (pin "5") (pinfunction "CLK_5") (pintype "input"))
      (node (ref "U1") (pin "10") (pinfunction "CLK_10") (pintype "output"))
    )
    (net (code "22") (name "Net-(J1-CMD)") (class "Default")
      (node (ref "J1") (pin "3") (pinfunction "CMD_3") (pintype "input"))
      (node (ref "U1") (pin "12") (pinfunction "CMD_12") (pintype "bidirectional"))
    )
    (net (code "23") (name "Net-(J1-D0)") (class "Default")
      (node (ref "J1") (pin "7") (pinfunction "D0_7") (pintype "bidirectional"))
      (node (ref "U1") (pin "16") (pinfunction "D0_16") (pintype "bidirectional"))
    )
    (net (code "24") (name "Net-(J1-D1)") (class "Default")
      (node (ref "J1") (pin "8") (pinfunction "D1_8") (pintype "bidirectional"))
      (node (ref "U1") (pin "18") (pinfunction "D1_18") (pintype "bidirectional"))
    )
    (net (code "25") (name "Net-(J1-D2)") (class "Default")
      (node (ref "J1") (pin "1") (pinfunction "D2_1") (pintype "bidirectional"))
      (node (ref "U1") (pin "22") (pinfunction "D2_22") (pintype "bidirectional"))
    )
    (net (code "26") (name "Net-(J1-D3)") (class "Default")
      (node (ref "J1") (pin "2") (pinfunction "D3_2") (pintype "bidirectional"))
      (node (ref "U1") (pin "24") (pinfunction "D3_24") (pintype "bidirectional"))
    )
    (net (code "27") (name "Net-(Q1-G)") (class "Default")
      (node (ref "Q1") (pin "1") (pinfunction "G_1") (pintype "passive"))
      (node (ref "R4") (pin "2") (pinfunction "2_2") (pintype "passive"))
      (node (ref "S2") (pin "1") (pinfunction "O_1") (pintype "passive"))
    )
    (net (code "28") (name "Net-(Q1-S)") (class "Default")
      (node (ref "D6") (pin "C") (pinfunction "C_C") (pintype "passive"))
      (node (ref "Q1") (pin "3") (pinfunction "S_3") (pintype "passive"))
      (node (ref "Q2") (pin "2") (pinfunction "D_2") (pintype "passive"))
    )
    (net (code "29") (name "Net-(S1-O)") (class "Default")
      (node (ref "R14") (pin "2") (pinfunction "2_2") (pintype "passive"))
      (node (ref "S1") (pin "1") (pinfunction "O_1") (pintype "passive"))
      (node (ref "U9") (pin "2") (pinfunction "SEL_2") (pintype "bidirectional"))
    )
    (net (code "30") (name "Net-(U1C-GPIO28)") (class "Default")
      (node (ref "R8") (pin "2") (pinfunction "2_2") (pintype "passive"))
      (node (ref "U1") (pin "28") (pinfunction "GPIO28_28") (pintype "bidirectional"))
    )
    (net (code "31") (name "Net-(U1C-GPIO29)") (class "Default")
      (node (ref "R3") (pin "2") (pinfunction "2_2") (pintype "passive"))
      (node (ref "U1") (pin "30") (pinfunction "GPIO29_30") (pintype "bidirectional"))
    )
    (net (code "32") (name "Net-(U1C-GPIO44)") (class "Default")
      (node (ref "R10") (pin "2") (pinfunction "2_2") (pintype "passive"))
      (node (ref "U1") (pin "82") (pinfunction "GPIO44_82") (pintype "bidirectional"))
    )
    (net (code "33") (name "Net-(U1C-GPIO45)") (class "Default")
      (node (ref "R9") (pin "2") (pinfunction "2_2") (pintype "passive"))
      (node (ref "U1") (pin "84") (pinfunction "GPIO45_84") (pintype "bidirectional"))
    )
    (net (code "34") (name "Net-(U1F-CLK+)") (class "Default")
      (node (ref "U1") (pin "113") (pinfunction "CLK+_113") (pintype "output"))
      (node (ref "U2") (pin "93") (pinfunction "CLK+_93") (pintype "input"))
    )
    (net (code "35") (name "Net-(U1F-CLK-)") (class "Default")
      (node (ref "U1") (pin "111") (pinfunction "CLK-_111") (pintype "output"))
      (node (ref "U2") (pin "94") (pinfunction "CLK-_94") (pintype "input"))
    )
    (net (code "36") (name "Net-(U1F-D0+)") (class "Default")
      (node (ref "U1") (pin "119") (pinfunction "D0+_119") (pintype "output"))
      (node (ref "U2") (pin "90") (pinfunction "D0+_90") (pintype "input"))
    )
    (net (code "37") (name "Net-(U1F-D0-)") (class "Default")
      (node (ref "U1") (pin "117") (pinfunction "D0-_117") (pintype "output"))
      (node (ref "U2") (pin "91") (pinfunction "D0-_91") (pintype "input"))
    )
    (net (code "38") (name "Net-(U1F-D1+)") (class "Default")
      (node (ref "U1") (pin "125") (pinfunction "D1+_125") (pintype "output"))
      (node (ref "U2") (pin "85") (pinfunction "D1+_85") (pintype "input"))
    )
    (net (code "39") (name "Net-(U1F-D1-)") (class "Default")
      (node (ref "U1") (pin "123") (pinfunction "D1-_123") (pintype "output"))
      (node (ref "U2") (pin "86") (pinfunction "D1-_86") (pintype "input"))
    )
    (net (code "40") (name "Net-(U1F-D2+)") (class "Default")
      (node (ref "U1") (pin "131") (pinfunction "D2+_131") (pintype "output"))
      (node (ref "U2") (pin "80") (pinfunction "D2+_80") (pintype "input"))
    )
    (net (code "41") (name "Net-(U1F-D2-)") (class "Default")
      (node (ref "U1") (pin "129") (pinfunction "D2-_129") (pintype "output"))
      (node (ref "U2") (pin "81") (pinfunction "D2-_81") (pintype "input"))
    )
    (net (code "42") (name "Net-(U2A-DE)") (class "Default")
      (node (ref "U2") (pin "46") (pinfunction "DE_46") (pintype "output"))
      (node (ref "U3") (pin "34") (pinfunction "DE_34") (pintype "input"))
    )
    (net (code "43") (name "Net-(U2A-HSYNC)") (class "Default")
      (node (ref "U2") (pin "48") (pinfunction "HSYNC_48") (pintype "output"))
      (node (ref "U3") (pin "32") (pinfunction "HSYNC_32") (pintype "input"))
    )
    (net (code "44") (name "Net-(U2A-ODCK)") (class "Default")
      (node (ref "U2") (pin "44") (pinfunction "ODCK_44") (pintype "output"))
      (node (ref "U3") (pin "30") (pinfunction "PCLK_30") (pintype "input"))
    )
    (net (code "45") (name "Net-(U2A-SCDT)") (class "Default")
      (node (ref "U2") (pin "8") (pinfunction "SCDT_8") (pintype "output"))
      (node (ref "U3") (pin "31") (pinfunction "ENABLE_31") (pintype "input"))
    )
    (net (code "46") (name "Net-(U2A-VSYNC)") (class "Default")
      (node (ref "U2") (pin "47") (pinfunction "VSYNC_47") (pintype "output"))
      (node (ref "U3") (pin "33") (pinfunction "VSYNC_33") (pintype "input"))
    )
    (net (code "47") (name "Net-(U2C-QB0)") (class "Default")
      (node (ref "U2") (pin "10") (pinfunction "QB0_10") (pintype "output"))
      (node (ref "U3") (pin "21") (pinfunction "B0_21") (pintype "input"))
    )
    (net (code "48") (name "Net-(U2C-QB1)") (class "Default")
      (node (ref "U2") (pin "11") (pinfunction "QB1_11") (pintype "output"))
      (node (ref "U3") (pin "22") (pinfunction "B1_22") (pintype "input"))
    )
    (net (code "49") (name "Net-(U2C-QB2)") (class "Default")
      (node (ref "U2") (pin "12") (pinfunction "QB2_12") (pintype "output"))
      (node (ref "U3") (pin "23") (pinfunction "B2_23") (pintype "input"))
    )
    (net (code "50") (name "Net-(U2C-QB3)") (class "Default")
      (node (ref "U2") (pin "13") (pinfunction "QB3_13") (pintype "output"))
      (node (ref "U3") (pin "24") (pinfunction "B3_24") (pintype "input"))
    )
    (net (code "51") (name "Net-(U2C-QB4)") (class "Default")
      (node (ref "U2") (pin "14") (pinfunction "QB4_14") (pintype "output"))
      (node (ref "U3") (pin "25") (pinfunction "B4_25") (pintype "input"))
    )
    (net (code "52") (name "Net-(U2C-QB5)") (class "Default")
      (node (ref "U2") (pin "15") (pinfunction "QB5_15") (pintype "output"))
      (node (ref "U3") (pin "26") (pinfunction "B5_26") (pintype "input"))
    )
    (net (code "53") (name "Net-(U2C-QB6)") (class "Default")
      (node (ref "U2") (pin "16") (pinfunction "QB6_16") (pintype "output"))
      (node (ref "U3") (pin "27") (pinfunction "B6_27") (pintype "input"))
    )
    (net (code "54") (name "Net-(U2C-QB7)") (class "Default")
      (node (ref "U2") (pin "17") (pinfunction "QB7_17") (pintype "output"))
      (node (ref "U3") (pin "28") (pinfunction "B7_28") (pintype "input"))
    )
    (net (code "55") (name "Net-(U2C-QG0)") (class "Default")
      (node (ref "U2") (pin "20") (pinfunction "QG0_20") (pintype "output"))
      (node (ref "U3") (pin "13") (pinfunction "G0_13") (pintype "input"))
    )
    (net (code "56") (name "Net-(U2C-QG1)") (class "Default")
      (node (ref "U2") (pin "21") (pinfunction "QG1_21") (pintype "output"))
      (node (ref "U3") (pin "14") (pinfunction "G1_14") (pintype "input"))
    )
    (net (code "57") (name "Net-(U2C-QG2)") (class "Default")
      (node (ref "U2") (pin "22") (pinfunction "QG2_22") (pintype "output"))
      (node (ref "U3") (pin "15") (pinfunction "G2_15") (pintype "input"))
    )
    (net (code "58") (name "Net-(U2C-QG3)") (class "Default")
      (node (ref "U2") (pin "23") (pinfunction "QG3_23") (pintype "output"))
      (node (ref "U3") (pin "16") (pinfunction "G3_16") (pintype "input"))
    )
    (net (code "59") (name "Net-(U2C-QG4)") (class "Default")
      (node (ref "U2") (pin "24") (pinfunction "QG4_24") (pintype "output"))
      (node (ref "U3") (pin "17") (pinfunction "G4_17") (pintype "input"))
    )
    (net (code "60") (name "Net-(U2C-QG5)") (class "Default")
      (node (ref "U2") (pin "25") (pinfunction "QG5_25") (pintype "output"))
      (node (ref "U3") (pin "18") (pinfunction "G5_18") (pintype "input"))
    )
    (net (code "61") (name "Net-(U2C-QG6)") (class "Default")
      (node (ref "U2") (pin "26") (pinfunction "QG6_26") (pintype "output"))
      (node (ref "U3") (pin "19") (pinfunction "G6_19") (pintype "input"))
    )
    (net (code "62") (name "Net-(U2C-QG7)") (class "Default")
      (node (ref "U2") (pin "27") (pinfunction "QG7_27") (pintype "output"))
      (node (ref "U3") (pin "20") (pinfunction "G7_20") (pintype "input"))
    )
    (net (code "63") (name "Net-(U2C-QR0)") (class "Default")
      (node (ref "U2") (pin "30") (pinfunction "QR0_30") (pintype "output"))
      (node (ref "U3") (pin "5") (pinfunction "R0_5") (pintype "input"))
    )
    (net (code "64") (name "Net-(U2C-QR1)") (class "Default")
      (node (ref "U2") (pin "31") (pinfunction "QR1_31") (pintype "output"))
      (node (ref "U3") (pin "6") (pinfunction "R1_6") (pintype "input"))
    )
    (net (code "65") (name "Net-(U2C-QR2)") (class "Default")
      (node (ref "U2") (pin "32") (pinfunction "QR2_32") (pintype "output"))
      (node (ref "U3") (pin "7") (pinfunction "R2_7") (pintype "input"))
    )
    (net (code "66") (name "Net-(U2C-QR3)") (class "Default")
      (node (ref "U2") (pin "33") (pinfunction "QR3_33") (pintype "output"))
      (node (ref "U3") (pin "8") (pinfunction "R3_8") (pintype "input"))
    )
    (net (code "67") (name "Net-(U2C-QR4)") (class "Default")
      (node (ref "U2") (pin "34") (pinfunction "QR4_34") (pintype "output"))
      (node (ref "U3") (pin "9") (pinfunction "R4_9") (pintype "input"))
    )
    (net (code "68") (name "Net-(U2C-QR5)") (class "Default")
      (node (ref "U2") (pin "35") (pinfunction "QR5_35") (pintype "output"))
      (node (ref "U3") (pin "10") (pinfunction "R5_10") (pintype "input"))
    )
    (net (code "69") (name "Net-(U2C-QR6)") (class "Default")
      (node (ref "U2") (pin "36") (pinfunction "QR6_36") (pintype "output"))
      (node (ref "U3") (pin "11") (pinfunction "R6_11") (pintype "input"))
    )
    (net (code "70") (name "Net-(U2C-QR7)") (class "Default")
      (node (ref "U2") (pin "37") (pinfunction "QR7_37") (pintype "output"))
      (node (ref "U3") (pin "12") (pinfunction "R7_12") (pintype "input"))
    )
    (net (code "71") (name "Net-(U4-PB3)") (class "Default")
      (node (ref "U4") (pin "2") (pinfunction "PB3_2") (pintype "bidirectional"))
      (node (ref "VR1") (pin "2") (pinfunction "S_2") (pintype "passive"))
    )
    (net (code "72") (name "Net-(U4-PB4)") (class "Default")
      (node (ref "U4") (pin "3") (pinfunction "PB4_3") (pintype "bidirectional"))
      (node (ref "U5") (pin "4") (pinfunction "CTRL_4") (pintype "input"))
    )
    (net (code "73") (name "Net-(U5-SW)") (class "Default")
      (node (ref "D1") (pin "A") (pinfunction "A_A") (pintype "passive"))
      (node (ref "L3") (pin "2") (pinfunction "2_2") (pintype "passive"))
      (node (ref "U5") (pin "1") (pinfunction "SW_1") (pintype "power_in"))
    )
    (net (code "74") (name "Net-(U6A-EN)") (class "Default")
      (node (ref "R1") (pin "1") (pinfunction "1_1") (pintype "passive"))
      (node (ref "U6") (pin "6") (pinfunction "EN_6") (pintype "input"))
      (node (ref "U7") (pin "6") (pinfunction "FLAG1_6") (pintype "output"))
    )
    (net (code "75") (name "Net-(U6A-LX)") (class "Default")
      (node (ref "L1") (pin "1") (pinfunction "1_1") (pintype "passive"))
      (node (ref "U6") (pin "8") (pinfunction "LX_8") (pintype "input"))
    )
    (net (code "76") (name "Net-(U6B-EN)") (class "Default")
      (node (ref "R2") (pin "1") (pinfunction "1_1") (pintype "passive"))
      (node (ref "U6") (pin "12") (pinfunction "EN_12") (pintype "input"))
      (node (ref "U7") (pin "5") (pinfunction "FLAG2_5") (pintype "output"))
    )
    (net (code "77") (name "Net-(U6B-LX)") (class "Default")
      (node (ref "L2") (pin "1") (pinfunction "1_1") (pintype "passive"))
      (node (ref "U6") (pin "2") (pinfunction "LX_2") (pintype "input"))
    )
    (net (code "78") (name "Net-(U7-EN)") (class "Default")
      (node (ref "C5") (pin "1") (pinfunction "1_1") (pintype "passive"))
      (node (ref "U7") (pin "3") (pinfunction "EN_3") (pintype "input"))
    )
    (net (code "79") (name "Net-(U9-D1+)") (class "Default")
      (node (ref "U9") (pin "7") (pinfunction "D1+_7") (pintype "bidirectional"))
      (node (ref "USB_A") (pin "D+") (pinfunction "D+_D+") (pintype "bidirectional"))
    )
    (net (code "80") (name "Net-(U9-D1-)") (class "Default")
      (node (ref "U9") (pin "6") (pinfunction "D1-_6") (pintype "bidirectional"))
      (node (ref "USB_A") (pin "D-") (pinfunction "D-_D-") (pintype "bidirectional"))
    )
    (net (code "81") (name "Net-(U9-D2+)") (class "Default")
      (node (ref "U9") (pin "9") (pinfunction "D2+_9") (pintype "bidirectional"))
      (node (ref "USB_B_1") (pin "3") (pinfunction "D+_3") (pintype "bidirectional"))
    )
    (net (code "82") (name "Net-(U9-D2-)") (class "Default")
      (node (ref "U9") (pin "8") (pinfunction "D2-_8") (pintype "bidirectional"))
      (node (ref "USB_B_1") (pin "2") (pinfunction "D-_2") (pintype "bidirectional"))
    )
    (net (code "83") (name "Net-(U11-IN)") (class "Default")
      (node (ref "U11") (pin "1") (pinfunction "IN_1") (pintype "power_in"))
      (node (ref "USB_B_2") (pin "1") (pinfunction "VCC_1") (pintype "power_in"))
    )
    (net (code "84") (name "Net-(U12-IN)") (class "Default")
      (node (ref "U12") (pin "1") (pinfunction "IN_1") (pintype "power_in"))
      (node (ref "USB_B_1") (pin "1") (pinfunction "VCC_1") (pintype "power_in"))
    )
    (net (code "85") (name "Net-(XB1-ASSOC{slash}AD5{slash}DIO5)") (class "Default")
      (node (ref "R16") (pin "2") (pinfunction "2_2") (pintype "passive"))
      (node (ref "XB1") (pin "15") (pinfunction "ASSOC/AD5/DIO5_15") (pintype "bidirectional"))
    )
    (net (code "86") (name "Net-(XB1-ON{slash}~{SLEEP})") (class "Default")
      (node (ref "R18") (pin "2") (pinfunction "2_2") (pintype "passive"))
      (node (ref "XB1") (pin "13") (pinfunction "ON/~{SLEEP}_13") (pintype "output"))
    )
    (net (code "87") (name "Net-(XB1-PWM0{slash}RSSI)") (class "Default")
      (node (ref "R17") (pin "2") (pinfunction "2_2") (pintype "passive"))
      (node (ref "XB1") (pin "6") (pinfunction "PWM0/RSSI_6") (pintype "output"))
    )
    (net (code "88") (name "RXD0") (class "Default")
      (node (ref "U1") (pin "53") (pinfunction "GPIO15_53") (pintype "bidirectional"))
      (node (ref "XB1") (pin "2") (pinfunction "DOUT_2") (pintype "output"))
    )
    (net (code "89") (name "SCL1") (class "Default")
      (node (ref "R12") (pin "2") (pinfunction "2_2") (pintype "passive"))
      (node (ref "U1") (pin "11") (pinfunction "GPIO3_11") (pintype "bidirectional"))
      (node (ref "U10") (pin "16") (pinfunction "SCL_16") (pintype "input"))
    )
    (net (code "90") (name "SDA1") (class "Default")
      (node (ref "R11") (pin "2") (pinfunction "2_2") (pintype "passive"))
      (node (ref "U1") (pin "9") (pinfunction "GPIO2_9") (pintype "bidirectional"))
      (node (ref "U10") (pin "15") (pinfunction "SDA_15") (pintype "bidirectional"))
    )
    (net (code "91") (name "TXD0") (class "Default")
      (node (ref "U1") (pin "51") (pinfunction "GPIO14_51") (pintype "bidirectional"))
      (node (ref "XB1") (pin "3") (pinfunction "DIN/~{CONFIG}_3") (pintype "input"))
    )
    (net (code "92") (name "USB_N") (class "Default")
      (node (ref "U1") (pin "167") (pinfunction "D-_167") (pintype "bidirectional"))
      (node (ref "U9") (pin "4") (pinfunction "D-_4") (pintype "bidirectional"))
    )
    (net (code "93") (name "USB_P") (class "Default")
      (node (ref "U1") (pin "165") (pinfunction "D+_165") (pintype "bidirectional"))
      (node (ref "U9") (pin "3") (pinfunction "D+_3") (pintype "bidirectional"))
    )
    (net (code "94") (name "VCC_1V8") (class "Default")
      (node (ref "C11") (pin "1") (pinfunction "1_1") (pintype "passive"))
      (node (ref "C2") (pin "+") (pinfunction "+_+") (pintype "passive"))
      (node (ref "L2") (pin "2") (pinfunction "2_2") (pintype "passive"))
      (node (ref "R5") (pin "2") (pinfunction "2_2") (pintype "passive"))
      (node (ref "S2") (pin "2") (pinfunction "P_2") (pintype "passive"))
      (node (ref "TP_1V8") (pin "P$1") (pinfunction "1_P$1") (pintype "bidirectional"))
      (node (ref "U1") (pin "183") (pinfunction "VCC_1V8_183") (pintype "power_in"))
      (node (ref "U1") (pin "184") (pinfunction "VCC_1V8_184") (pintype "power_in"))
      (node (ref "U1") (pin "185") (pinfunction "VCC_1V8_185") (pintype "power_in"))
      (node (ref "U1") (pin "186") (pinfunction "VCC_1V8_186") (pintype "power_in"))
      (node (ref "U6") (pin "10") (pinfunction "FB_10") (pintype "input"))
    )
    (net (code "95") (name "VCC_3V3") (class "Default")
      (node (ref "C1") (pin "+") (pinfunction "+_+") (pintype "passive"))
      (node (ref "C10") (pin "2") (pinfunction "2_2") (pintype "passive"))
      (node (ref "C12") (pin "1") (pinfunction "1_1") (pintype "passive"))
      (node (ref "C15") (pin "1") (pinfunction "1_1") (pintype "passive"))
      (node (ref "C16") (pin "1") (pinfunction "1_1") (pintype "passive"))
      (node (ref "C17") (pin "1") (pinfunction "1_1") (pintype "passive"))
      (node (ref "C18") (pin "A") (pinfunction "+_A") (pintype "passive"))
      (node (ref "C19") (pin "A") (pinfunction "+_A") (pintype "passive"))
      (node (ref "C20") (pin "A") (pinfunction "+_A") (pintype "passive"))
      (node (ref "C21") (pin "1") (pinfunction "1_1") (pintype "passive"))
      (node (ref "C22") (pin "1") (pinfunction "1_1") (pintype "passive"))
      (node (ref "C9") (pin "1") (pinfunction "1_1") (pintype "passive"))
      (node (ref "J1") (pin "4") (pinfunction "VCC_4") (pintype "power_in"))
      (node (ref "L1") (pin "2") (pinfunction "2_2") (pintype "passive"))
      (node (ref "R11") (pin "1") (pinfunction "1_1") (pintype "passive"))
      (node (ref "R12") (pin "1") (pinfunction "1_1") (pintype "passive"))
      (node (ref "R14") (pin "1") (pinfunction "1_1") (pintype "passive"))
      (node (ref "R15") (pin "1") (pinfunction "1_1") (pintype "passive"))
      (node (ref "R20") (pin "2") (pinfunction "2_2") (pintype "passive"))
      (node (ref "R7") (pin "1") (pinfunction "1_1") (pintype "passive"))
      (node (ref "TP_3V3") (pin "P$1") (pinfunction "1_P$1") (pintype "bidirectional"))
      (node (ref "U$1") (pin "2") (pinfunction "SW-_2") (pintype "bidirectional"))
      (node (ref "U1") (pin "189") (pinfunction "VDAC_189") (pintype "power_in"))
      (node (ref "U1") (pin "190") (pinfunction "VDAC_190") (pintype "power_in"))
      (node (ref "U1") (pin "191") (pinfunction "VCC_3V3_191") (pintype "power_in"))
      (node (ref "U1") (pin "192") (pinfunction "VCC_3V3_192") (pintype "power_in"))
      (node (ref "U1") (pin "193") (pinfunction "VCC_3V3_193") (pintype "power_in"))
      (node (ref "U1") (pin "194") (pinfunction "VCC_3V3_194") (pintype "power_in"))
      (node (ref "U1") (pin "39") (pinfunction "VDD_GPIO0_27_39") (pintype "power_in"))
      (node (ref "U1") (pin "4") (pinfunction "VDD_SDX_4") (pintype "power_in"))
      (node (ref "U1") (pin "40") (pinfunction "VDD_GPIO0_27_40") (pintype "power_in"))
      (node (ref "U1") (pin "41") (pinfunction "VDD_GPIO28_45_41") (pintype "power_in"))
      (node (ref "U1") (pin "42") (pinfunction "VDD_GPIO28_45_42") (pintype "power_in"))
      (node (ref "U1") (pin "6") (pinfunction "VDD_SDX_6") (pintype "power_in"))
      (node (ref "U10") (pin "2") (pinfunction "VCC_2") (pintype "power_in"))
      (node (ref "U2") (pin "18") (pinfunction "OVDD_18") (pintype "power_in"))
      (node (ref "U2") (pin "29") (pinfunction "OVDD_29") (pintype "power_in"))
      (node (ref "U2") (pin "3") (pinfunction "ST_3") (pintype "input"))
      (node (ref "U2") (pin "38") (pinfunction "DVDD_38") (pintype "power_in"))
      (node (ref "U2") (pin "43") (pinfunction "OVDD_43") (pintype "power_in"))
      (node (ref "U2") (pin "57") (pinfunction "OVDD_57") (pintype "power_in"))
      (node (ref "U2") (pin "6") (pinfunction "DVDD_6") (pintype "power_in"))
      (node (ref "U2") (pin "67") (pinfunction "DVDD_67") (pintype "power_in"))
      (node (ref "U2") (pin "7") (pinfunction "~{STAG}_7") (pintype "input"))
      (node (ref "U2") (pin "78") (pinfunction "OVDD_78") (pintype "power_in"))
      (node (ref "U2") (pin "82") (pinfunction "AVDD_82") (pintype "power_in"))
      (node (ref "U2") (pin "84") (pinfunction "AVDD_84") (pintype "power_in"))
      (node (ref "U2") (pin "88") (pinfunction "AVDD_88") (pintype "power_in"))
      (node (ref "U2") (pin "95") (pinfunction "AVDD_95") (pintype "power_in"))
      (node (ref "U2") (pin "97") (pinfunction "PVDD_97") (pintype "power_in"))
      (node (ref "U2") (pin "99") (pinfunction "RSVD_99") (pintype "bidirectional"))
      (node (ref "U3") (pin "4") (pinfunction "VDD_4") (pintype "power_in"))
      (node (ref "U6") (pin "4") (pinfunction "FB_4") (pintype "input"))
      (node (ref "U9") (pin "1") (pinfunction "VCC_1") (pintype "bidirectional"))
      (node (ref "XB1") (pin "1") (pinfunction "VCC_1") (pintype "power_in"))
    )
    (net (code "96") (name "VCC_5V0") (class "Default")
      (node (ref "C13") (pin "1") (pinfunction "1_1") (pintype "passive"))
      (node (ref "C14") (pin "1") (pinfunction "1_1") (pintype "passive"))
      (node (ref "C3") (pin "+") (pinfunction "+_+") (pintype "passive"))
      (node (ref "C4") (pin "+") (pinfunction "+_+") (pintype "passive"))
      (node (ref "C7") (pin "1") (pinfunction "1_1") (pintype "passive"))
      (node (ref "C8") (pin "1") (pinfunction "1_1") (pintype "passive"))
      (node (ref "J3") (pin "2") (pinfunction "2_2") (pintype "passive"))
      (node (ref "L3") (pin "1") (pinfunction "1_1") (pintype "passive"))
      (node (ref "R1") (pin "2") (pinfunction "2_2") (pintype "passive"))
      (node (ref "R19") (pin "2") (pinfunction "2_2") (pintype "passive"))
      (node (ref "R2") (pin "2") (pinfunction "2_2") (pintype "passive"))
      (node (ref "R21") (pin "2") (pinfunction "2_2") (pintype "passive"))
      (node (ref "R22") (pin "2") (pinfunction "2_2") (pintype "passive"))
      (node (ref "TP_5V0") (pin "P$1") (pinfunction "1_P$1") (pintype "bidirectional"))
      (node (ref "U1") (pin "197") (pinfunction "VBAT_197") (pintype "power_in"))
      (node (ref "U1") (pin "198") (pinfunction "VBAT_198") (pintype "power_in"))
      (node (ref "U1") (pin "199") (pinfunction "VBAT_199") (pintype "power_in"))
      (node (ref "U1") (pin "200") (pinfunction "VBAT_200") (pintype "power_in"))
      (node (ref "U11") (pin "5") (pinfunction "OUT_5") (pintype "power_in"))
      (node (ref "U12") (pin "5") (pinfunction "OUT_5") (pintype "power_in"))
      (node (ref "U4") (pin "8") (pinfunction "VCC_8") (pintype "power_in"))
      (node (ref "U5") (pin "5") (pinfunction "VIN_5") (pintype "power_in"))
      (node (ref "U6") (pin "1") (pinfunction "VIN_1") (pintype "input"))
      (node (ref "U6") (pin "7") (pinfunction "VIN_7") (pintype "input"))
      (node (ref "U7") (pin "1") (pinfunction "VCC_1") (pintype "power_in"))
      (node (ref "U8") (pin "4") (pinfunction "VCC_4") (pintype "power_in"))
      (node (ref "USB_A") (pin "VBUS") (pinfunction "VCC_VBUS") (pintype "power_in"))
      (node (ref "VR1") (pin "3") (pinfunction "E_3") (pintype "passive"))
    )
    (net (code "97") (name "XBEE_SLEEP_RQ") (class "Default")
      (node (ref "U1") (pin "77") (pinfunction "GPIO23_77") (pintype "bidirectional"))
      (node (ref "XB1") (pin "9") (pinfunction "~{DTR}/SLEEP_RQ/DI8_9") (pintype "bidirectional"))
    )
    (net (code "98") (name "unconnected-(S1-S-Pad3)") (class "Default")
      (node (ref "S1") (pin "3") (pinfunction "S_3") (pintype "passive"))
    )
    (net (code "99") (name "unconnected-(S2-S-Pad3)") (class "Default")
      (node (ref "S2") (pin "3") (pinfunction "S_3") (pintype "passive"))
    )
    (net (code "100") (name "unconnected-(U1C-GPIO0-Pad3)") (class "Default")
      (node (ref "U1") (pin "3") (pinfunction "GPIO0_3") (pintype "bidirectional"))
    )
    (net (code "101") (name "unconnected-(U1C-GPIO1-Pad5)") (class "Default")
      (node (ref "U1") (pin "5") (pinfunction "GPIO1_5") (pintype "bidirectional"))
    )
    (net (code "102") (name "unconnected-(U1C-GPIO4-Pad15)") (class "Default")
      (node (ref "U1") (pin "15") (pinfunction "GPIO4_15") (pintype "bidirectional"))
    )
    (net (code "103") (name "unconnected-(U1C-GPIO5-Pad17)") (class "Default")
      (node (ref "U1") (pin "17") (pinfunction "GPIO5_17") (pintype "bidirectional"))
    )
    (net (code "104") (name "unconnected-(U1C-GPIO6-Pad21)") (class "Default")
      (node (ref "U1") (pin "21") (pinfunction "GPIO6_21") (pintype "bidirectional"))
    )
    (net (code "105") (name "unconnected-(U1C-GPIO7-Pad23)") (class "Default")
      (node (ref "U1") (pin "23") (pinfunction "GPIO7_23") (pintype "bidirectional"))
    )
    (net (code "106") (name "unconnected-(U1C-GPIO8-Pad27)") (class "Default")
      (node (ref "U1") (pin "27") (pinfunction "GPIO8_27") (pintype "bidirectional"))
    )
    (net (code "107") (name "unconnected-(U1C-GPIO9-Pad29)") (class "Default")
      (node (ref "U1") (pin "29") (pinfunction "GPIO9_29") (pintype "bidirectional"))
    )
    (net (code "108") (name "unconnected-(U1C-GPIO10-Pad33)") (class "Default")
      (node (ref "U1") (pin "33") (pinfunction "GPIO10_33") (pintype "bidirectional"))
    )
    (net (code "109") (name "unconnected-(U1C-GPIO11-Pad35)") (class "Default")
      (node (ref "U1") (pin "35") (pinfunction "GPIO11_35") (pintype "bidirectional"))
    )
    (net (code "110") (name "unconnected-(U1C-GPIO12-Pad45)") (class "Default")
      (node (ref "U1") (pin "45") (pinfunction "GPIO12_45") (pintype "bidirectional"))
    )
    (net (code "111") (name "unconnected-(U1C-GPIO13-Pad47)") (class "Default")
      (node (ref "U1") (pin "47") (pinfunction "GPIO13_47") (pintype "bidirectional"))
    )
    (net (code "112") (name "unconnected-(U1C-GPIO16-Pad57)") (class "Default")
      (node (ref "U1") (pin "57") (pinfunction "GPIO16_57") (pintype "bidirectional"))
    )
    (net (code "113") (name "unconnected-(U1C-GPIO17-Pad59)") (class "Default")
      (node (ref "U1") (pin "59") (pinfunction "GPIO17_59") (pintype "bidirectional"))
    )
    (net (code "114") (name "unconnected-(U1C-GPIO18-Pad63)") (class "Default")
      (node (ref "U1") (pin "63") (pinfunction "GPIO18_63") (pintype "bidirectional"))
    )
    (net (code "115") (name "unconnected-(U1C-GPIO19-Pad65)") (class "Default")
      (node (ref "U1") (pin "65") (pinfunction "GPIO19_65") (pintype "bidirectional"))
    )
    (net (code "116") (name "unconnected-(U1C-GPIO24-Pad81)") (class "Default")
      (node (ref "U1") (pin "81") (pinfunction "GPIO24_81") (pintype "bidirectional"))
    )
    (net (code "117") (name "unconnected-(U1C-GPIO25-Pad83)") (class "Default")
      (node (ref "U1") (pin "83") (pinfunction "GPIO25_83") (pintype "bidirectional"))
    )
    (net (code "118") (name "unconnected-(U1C-GPIO26-Pad87)") (class "Default")
      (node (ref "U1") (pin "87") (pinfunction "GPIO26_87") (pintype "bidirectional"))
    )
    (net (code "119") (name "unconnected-(U1C-GPIO27-Pad89)") (class "Default")
      (node (ref "U1") (pin "89") (pinfunction "GPIO27_89") (pintype "bidirectional"))
    )
    (net (code "120") (name "unconnected-(U1C-GPIO30-Pad34)") (class "Default")
      (node (ref "U1") (pin "34") (pinfunction "GPIO30_34") (pintype "bidirectional"))
    )
    (net (code "121") (name "unconnected-(U1C-GPIO31-Pad36)") (class "Default")
      (node (ref "U1") (pin "36") (pinfunction "GPIO31_36") (pintype "bidirectional"))
    )
    (net (code "122") (name "unconnected-(U1C-GPIO32-Pad46)") (class "Default")
      (node (ref "U1") (pin "46") (pinfunction "GPIO32_46") (pintype "bidirectional"))
    )
    (net (code "123") (name "unconnected-(U1C-GPIO33-Pad48)") (class "Default")
      (node (ref "U1") (pin "48") (pinfunction "GPIO33_48") (pintype "bidirectional"))
    )
    (net (code "124") (name "unconnected-(U1C-GPIO34-Pad52)") (class "Default")
      (node (ref "U1") (pin "52") (pinfunction "GPIO34_52") (pintype "bidirectional"))
    )
    (net (code "125") (name "unconnected-(U1C-GPIO35-Pad54)") (class "Default")
      (node (ref "U1") (pin "54") (pinfunction "GPIO35_54") (pintype "bidirectional"))
    )
    (net (code "126") (name "unconnected-(U1C-GPIO36-Pad58)") (class "Default")
      (node (ref "U1") (pin "58") (pinfunction "GPIO36_58") (pintype "bidirectional"))
    )
    (net (code "127") (name "unconnected-(U1C-GPIO37-Pad60)") (class "Default")
      (node (ref "U1") (pin "60") (pinfunction "GPIO37_60") (pintype "bidirectional"))
    )
    (net (code "128") (name "unconnected-(U1C-GPIO38-Pad64)") (class "Default")
      (node (ref "U1") (pin "64") (pinfunction "GPIO38_64") (pintype "bidirectional"))
    )
    (net (code "129") (name "unconnected-(U1C-GPIO39-Pad66)") (class "Default")
      (node (ref "U1") (pin "66") (pinfunction "GPIO39_66") (pintype "bidirectional"))
    )
    (net (code "130") (name "unconnected-(U1C-GPIO40-Pad70)") (class "Default")
      (node (ref "U1") (pin "70") (pinfunction "GPIO40_70") (pintype "bidirectional"))
    )
    (net (code "131") (name "unconnected-(U1C-GPIO41-Pad72)") (class "Default")
      (node (ref "U1") (pin "72") (pinfunction "GPIO41_72") (pintype "bidirectional"))
    )
    (net (code "132") (name "unconnected-(U1C-GPIO42-Pad76)") (class "Default")
      (node (ref "U1") (pin "76") (pinfunction "GPIO42_76") (pintype "bidirectional"))
    )
    (net (code "133") (name "unconnected-(U1C-GPIO43-Pad78)") (class "Default")
      (node (ref "U1") (pin "78") (pinfunction "GPIO43_78") (pintype "bidirectional"))
    )
    (net (code "134") (name "unconnected-(U1C-RUN-Pad177)") (class "Default")
      (node (ref "U1") (pin "177") (pinfunction "RUN_177") (pintype "input"))
    )
    (net (code "135") (name "unconnected-(U1C-TVDAC-Pad166)") (class "Default")
      (node (ref "U1") (pin "166") (pinfunction "TVDAC_166") (pintype "output"))
    )
    (net (code "136") (name "unconnected-(U1C-VDD_CORE-Pad179)") (class "Default")
      (node (ref "U1") (pin "179") (pinfunction "VDD_CORE_179") (pintype "no_connect"))
    )
    (net (code "137") (name "unconnected-(U1F-CEC-Pad171)") (class "Default")
      (node (ref "U1") (pin "171") (pinfunction "CEC_171") (pintype "bidirectional"))
    )
    (net (code "138") (name "unconnected-(U1F-~{HPD}-Pad88)") (class "Default")
      (node (ref "U1") (pin "88") (pinfunction "~{HPD}_88") (pintype "input"))
    )
    (net (code "139") (name "unconnected-(U2B-CTL1-Pad40)") (class "Default")
      (node (ref "U2") (pin "40") (pinfunction "CTL1_40") (pintype "output"))
    )
    (net (code "140") (name "unconnected-(U2B-CTL2-Pad41)") (class "Default")
      (node (ref "U2") (pin "41") (pinfunction "CTL2_41") (pintype "output"))
    )
    (net (code "141") (name "unconnected-(U2B-CTL3-Pad42)") (class "Default")
      (node (ref "U2") (pin "42") (pinfunction "CTL3_42") (pintype "output"))
    )
    (net (code "142") (name "unconnected-(U2B-EXT_RES-Pad96)") (class "Default")
      (node (ref "U2") (pin "96") (pinfunction "EXT_RES_96") (pintype "input"))
    )
    (net (code "143") (name "unconnected-(U2B-~{PDO}-Pad9)") (class "Default")
      (node (ref "U2") (pin "9") (pinfunction "~{PDO}_9") (pintype "input"))
    )
    (net (code "144") (name "unconnected-(U2B-~{PD}-Pad2)") (class "Default")
      (node (ref "U2") (pin "2") (pinfunction "~{PD}_2") (pintype "input"))
    )
    (net (code "145") (name "unconnected-(U3-X+-Pad37)") (class "Default")
      (node (ref "U3") (pin "37") (pinfunction "X+_37") (pintype "output"))
    )
    (net (code "146") (name "unconnected-(U3-X--Pad39)") (class "Default")
      (node (ref "U3") (pin "39") (pinfunction "X-_39") (pintype "output"))
    )
    (net (code "147") (name "unconnected-(U3-Y+-Pad38)") (class "Default")
      (node (ref "U3") (pin "38") (pinfunction "Y+_38") (pintype "output"))
    )
    (net (code "148") (name "unconnected-(U3-Y--Pad40)") (class "Default")
      (node (ref "U3") (pin "40") (pinfunction "Y-_40") (pintype "output"))
    )
    (net (code "149") (name "unconnected-(U7-FLAG3-Pad4)") (class "Default")
      (node (ref "U7") (pin "4") (pinfunction "FLAG3_4") (pintype "output"))
    )
    (net (code "150") (name "unconnected-(U10-32KHZ-Pad1)") (class "Default")
      (node (ref "U10") (pin "1") (pinfunction "32KHZ_1") (pintype "output"))
    )
    (net (code "151") (name "unconnected-(U10-RST-Pad4)") (class "Default")
      (node (ref "U10") (pin "4") (pinfunction "RST_4") (pintype "bidirectional"))
    )
    (net (code "152") (name "unconnected-(U10-~{INT}{slash}SQW-Pad3)") (class "Default")
      (node (ref "U10") (pin "3") (pinfunction "~{INT}/SQW_3") (pintype "output"))
    )
    (net (code "153") (name "unconnected-(U11-STAT-Pad4)") (class "Default")
      (node (ref "U11") (pin "4") (pinfunction "STAT_4") (pintype "output"))
    )
    (net (code "154") (name "unconnected-(U12-STAT-Pad4)") (class "Default")
      (node (ref "U12") (pin "4") (pinfunction "STAT_4") (pintype "output"))
    )
    (net (code "155") (name "unconnected-(USB_B_1-ID-Pad4)") (class "Default")
      (node (ref "USB_B_1") (pin "4") (pinfunction "ID_4") (pintype "bidirectional"))
    )
    (net (code "156") (name "unconnected-(USB_B_2-D+-Pad3)") (class "Default")
      (node (ref "USB_B_2") (pin "3") (pinfunction "D+_3") (pintype "bidirectional"))
    )
    (net (code "157") (name "unconnected-(USB_B_2-D--Pad2)") (class "Default")
      (node (ref "USB_B_2") (pin "2") (pinfunction "D-_2") (pintype "bidirectional"))
    )
    (net (code "158") (name "unconnected-(USB_B_2-ID-Pad4)") (class "Default")
      (node (ref "USB_B_2") (pin "4") (pinfunction "ID_4") (pintype "bidirectional"))
    )
    (net (code "159") (name "unconnected-(XB1-AD0{slash}DIO0-Pad20)") (class "Default")
      (node (ref "XB1") (pin "20") (pinfunction "AD0/DIO0_20") (pintype "bidirectional"))
    )
    (net (code "160") (name "unconnected-(XB1-AD1{slash}DIO1-Pad19)") (class "Default")
      (node (ref "XB1") (pin "19") (pinfunction "AD1/DIO1_19") (pintype "bidirectional"))
    )
    (net (code "161") (name "unconnected-(XB1-AD2{slash}DIO2-Pad18)") (class "Default")
      (node (ref "XB1") (pin "18") (pinfunction "AD2/DIO2_18") (pintype "bidirectional"))
    )
    (net (code "162") (name "unconnected-(XB1-CD{slash}DOUT_EN{slash}DO8-Pad4)") (class "Default")
      (node (ref "XB1") (pin "4") (pinfunction "CD/DOUT_EN/DO8_4") (pintype "output"))
    )
    (net (code "163") (name "unconnected-(XB1-COORD_SEL{slash}AD3{slash}DIO3-Pad17)") (class "Default")
      (node (ref "XB1") (pin "17") (pinfunction "COORD_SEL/AD3/DIO3_17") (pintype "bidirectional"))
    )
    (net (code "164") (name "unconnected-(XB1-RF_TX{slash}AD4{slash}DIO4-Pad11)") (class "Default")
      (node (ref "XB1") (pin "11") (pinfunction "RF_TX/AD4/DIO4_11") (pintype "bidirectional"))
    )
    (net (code "165") (name "unconnected-(XB1-VREF-Pad14)") (class "Default")
      (node (ref "XB1") (pin "14") (pinfunction "VREF_14") (pintype "input"))
    )
    (net (code "166") (name "unconnected-(XB1-~{CTS}{slash}DIO7-Pad12)") (class "Default")
      (node (ref "XB1") (pin "12") (pinfunction "~{CTS}/DIO7_12") (pintype "bidirectional"))
    )
    (net (code "167") (name "unconnected-(XB1-~{RESET}-Pad5)") (class "Default")
      (node (ref "XB1") (pin "5") (pinfunction "~{RESET}_5") (pintype "input"))
    )
    (net (code "168") (name "unconnected-(XB1-~{RTS}{slash}AD6{slash}DIO6-Pad16)") (class "Default")
      (node (ref "XB1") (pin "16") (pinfunction "~{RTS}/AD6/DIO6_16") (pintype "bidirectional"))
    )
  )
)
